# RK3566.net
KiCad netlist of a schematic drawn in Altium Designer
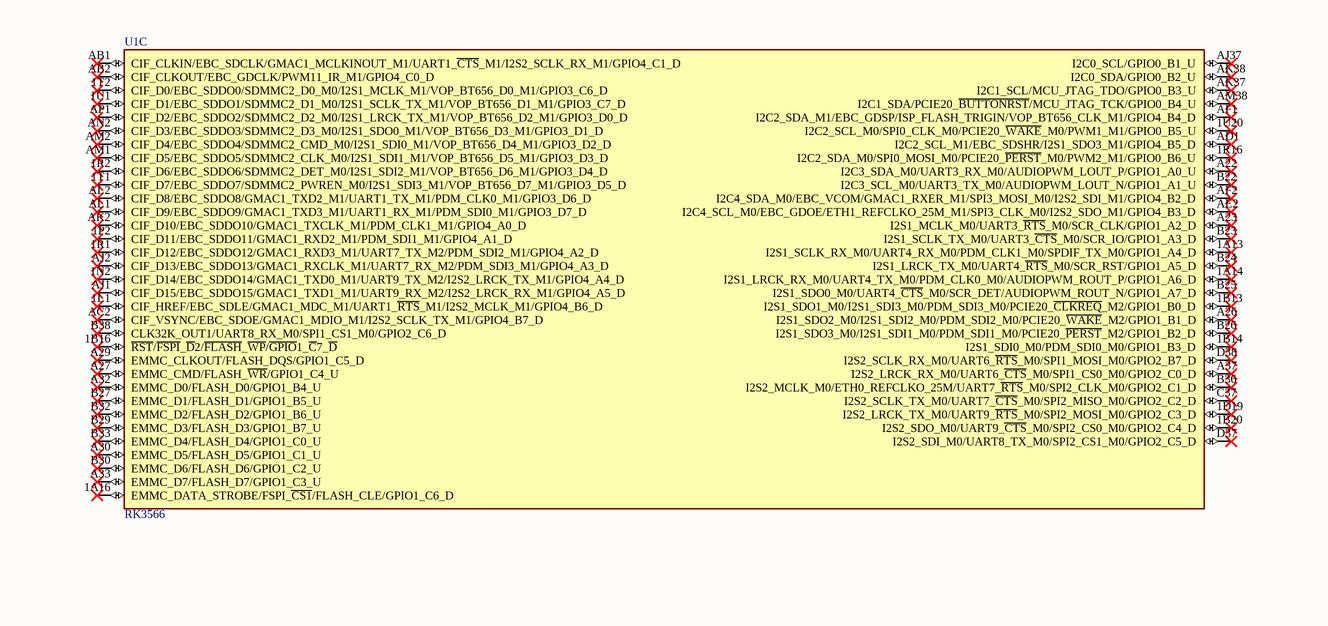
[diagram p0: RK3566.SchDoc, top left]
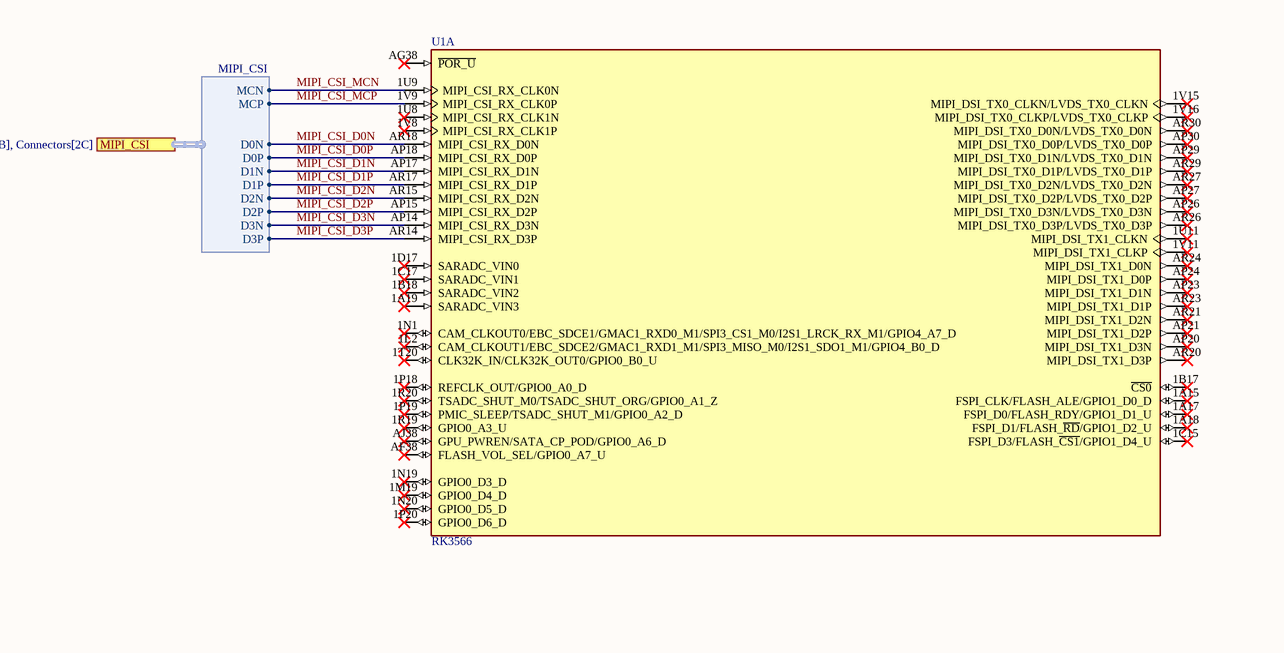
[diagram p1: RK3566.SchDoc, top right]
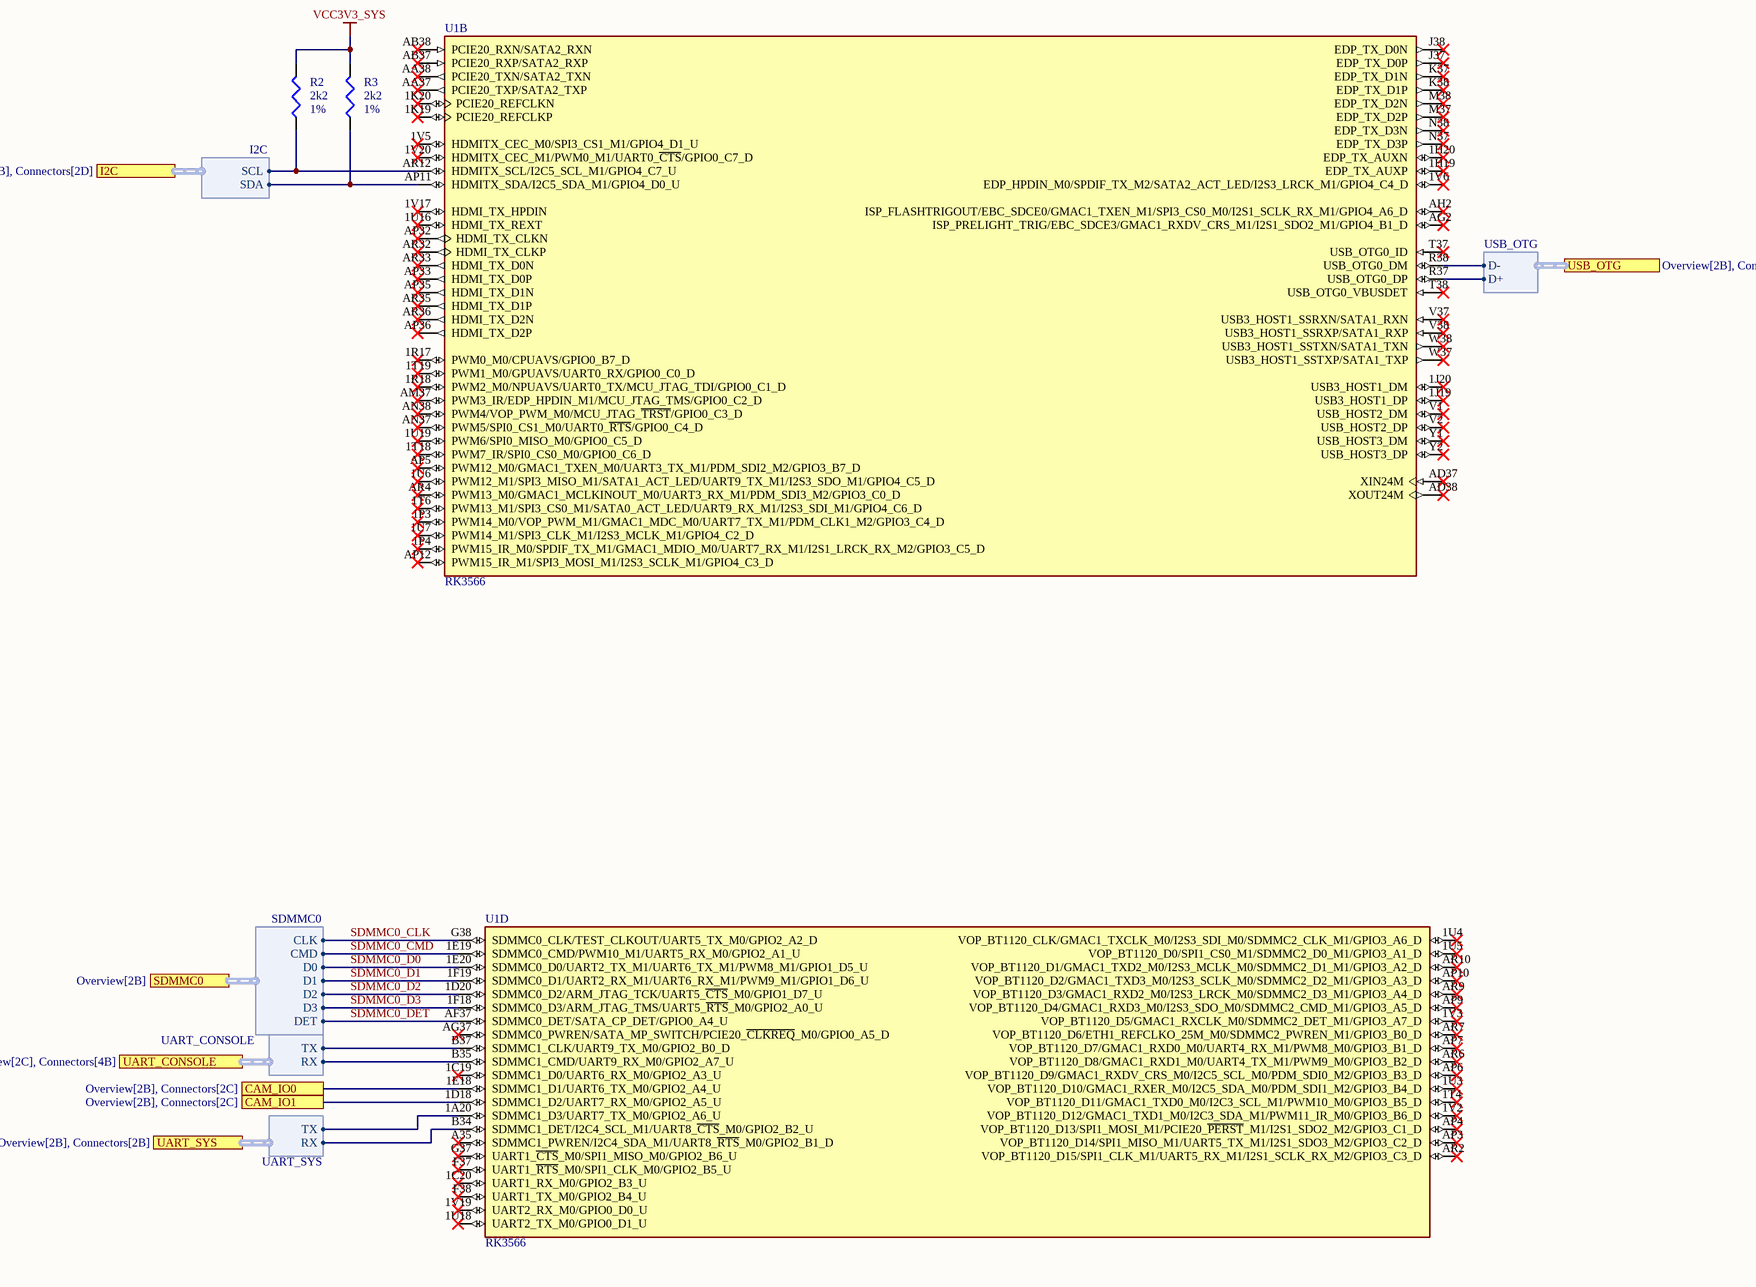
[diagram p2: RK3566.SchDoc, bottom left]
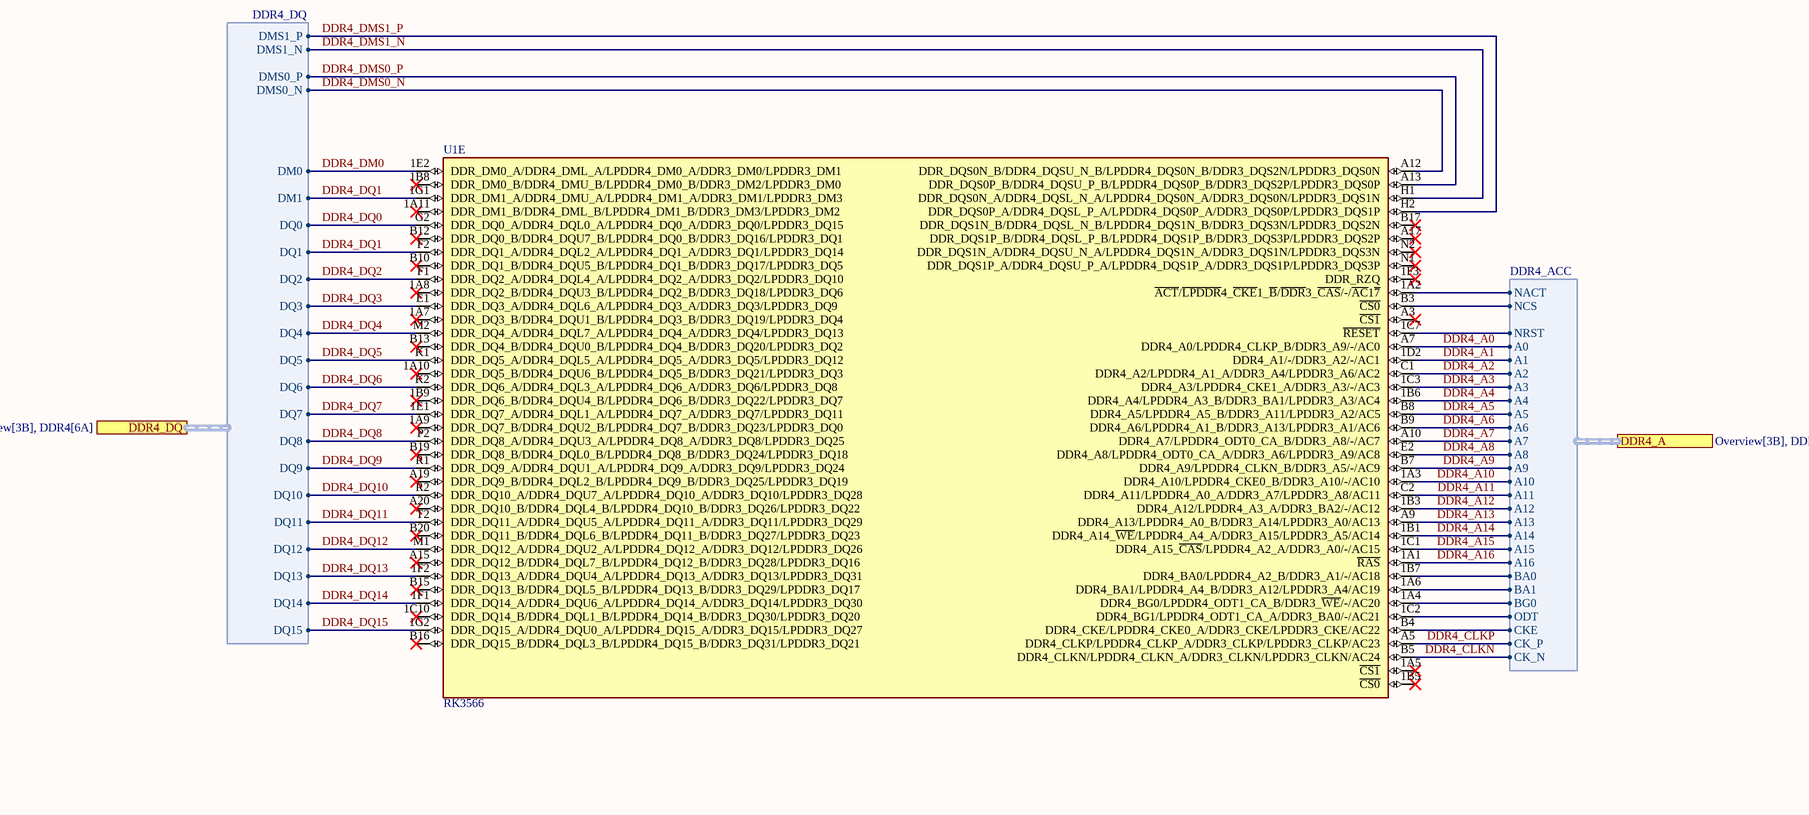
[diagram p3: RK3566.SchDoc, bottom right]

(export (version "E")
  (design (tool "Eeschema 10.0.6"))
  (components
    (comp (ref "R2")
      (value "2k2")
      (footprint "RC0402FR-075K6L")
      (description "RES 2.2k 1% 62.5mW 0402")
      (fields (field (name "TOLERANCE") "1%") (field (name "Comment") "RES 2.2K"))
      (libsource (lib "PersonalAltiumLibrary") (part "RES 2.2K"))
    )
    (comp (ref "R3")
      (value "2k2")
      (footprint "RC0402FR-075K6L")
      (description "RES 2.2k 1% 62.5mW 0402")
      (fields (field (name "TOLERANCE") "1%") (field (name "Comment") "RES 2.2K"))
      (libsource (lib "PersonalAltiumLibrary") (part "RES 2.2K"))
    )
    (comp (ref "U1")
      (value "RK3566")
      (footprint "RK3566")
      (description "high-performance and low-power quad-core application processor")
      (fields (field (name "MF") "Fuzhou Rockchip Electronics Co"))
      (libsource (lib "PersonalAltiumLibrary") (part "RK3566"))
    )
  )
  (nets
    (net (code "9") (name "/BA0") (class "Default")
      (node (ref "U1") (pin "1B7") (pinfunction "DDR4_BA0/LPDDR4_A2_B/DDR3_A1/-/AC18_1B7") (pintype "bidirectional"))
    )
    (net (code "10") (name "/BA1") (class "Default")
      (node (ref "U1") (pin "1A6") (pinfunction "DDR4_BA1/LPDDR4_A4_B/DDR3_A12/LPDDR3_A4/AC19_1A6") (pintype "bidirectional"))
    )
    (net (code "11") (name "/BG0") (class "Default")
      (node (ref "U1") (pin "1A4") (pinfunction "DDR4_BG0/LPDDR4_ODT1_CA_B/DDR3_~{WE}/-/AC20_1A4") (pintype "bidirectional"))
    )
    (net (code "12") (name "/CAM_IO0") (class "Default")
      (node (ref "U1") (pin "1E18") (pinfunction "SDMMC1_D1/UART6_TX_M0/GPIO2_A4_U_1E18") (pintype "bidirectional"))
    )
    (net (code "13") (name "/CAM_IO1") (class "Default")
      (node (ref "U1") (pin "1D18") (pinfunction "SDMMC1_D2/UART7_RX_M0/GPIO2_A5_U_1D18") (pintype "bidirectional"))
    )
    (net (code "14") (name "/CKE") (class "Default")
      (node (ref "U1") (pin "B4") (pinfunction "DDR4_CKE/LPDDR4_CKE0_A/DDR3_CKE/LPDDR3_CKE/AC22_B4") (pintype "bidirectional"))
    )
    (net (code "15") (name "/D+") (class "Default")
      (node (ref "U1") (pin "R37") (pinfunction "USB_OTG0_DP_R37") (pintype "bidirectional"))
    )
    (net (code "16") (name "/D-") (class "Default")
      (node (ref "U1") (pin "R38") (pinfunction "USB_OTG0_DM_R38") (pintype "bidirectional"))
    )
    (net (code "17") (name "/DDR4_A0") (class "Default")
      (node (ref "U1") (pin "A7") (pinfunction "DDR4_A0/LPDDR4_CLKP_B/DDR3_A9/-/AC0_A7") (pintype "bidirectional"))
    )
    (net (code "18") (name "/DDR4_A1") (class "Default")
      (node (ref "U1") (pin "1D2") (pinfunction "DDR4_A1/-/DDR3_A2/-/AC1_1D2") (pintype "bidirectional"))
    )
    (net (code "19") (name "/DDR4_A2") (class "Default")
      (node (ref "U1") (pin "C1") (pinfunction "DDR4_A2/LPDDR4_A1_A/DDR3_A4/LPDDR3_A6/AC2_C1") (pintype "bidirectional"))
    )
    (net (code "20") (name "/DDR4_A3") (class "Default")
      (node (ref "U1") (pin "1C3") (pinfunction "DDR4_A3/LPDDR4_CKE1_A/DDR3_A3/-/AC3_1C3") (pintype "bidirectional"))
    )
    (net (code "21") (name "/DDR4_A4") (class "Default")
      (node (ref "U1") (pin "1B6") (pinfunction "DDR4_A4/LPDDR4_A3_B/DDR3_BA1/LPDDR3_A3/AC4_1B6") (pintype "bidirectional"))
    )
    (net (code "22") (name "/DDR4_A5") (class "Default")
      (node (ref "U1") (pin "B8") (pinfunction "DDR4_A5/LPDDR4_A5_B/DDR3_A11/LPDDR3_A2/AC5_B8") (pintype "bidirectional"))
    )
    (net (code "23") (name "/DDR4_A6") (class "Default")
      (node (ref "U1") (pin "B9") (pinfunction "DDR4_A6/LPDDR4_A1_B/DDR3_A13/LPDDR3_A1/AC6_B9") (pintype "bidirectional"))
    )
    (net (code "24") (name "/DDR4_A7") (class "Default")
      (node (ref "U1") (pin "A10") (pinfunction "DDR4_A7/LPDDR4_ODT0_CA_B/DDR3_A8/-/AC7_A10") (pintype "bidirectional"))
    )
    (net (code "25") (name "/DDR4_A8") (class "Default")
      (node (ref "U1") (pin "E2") (pinfunction "DDR4_A8/LPDDR4_ODT0_CA_A/DDR3_A6/LPDDR3_A9/AC8_E2") (pintype "bidirectional"))
    )
    (net (code "26") (name "/DDR4_A9") (class "Default")
      (node (ref "U1") (pin "B7") (pinfunction "DDR4_A9/LPDDR4_CLKN_B/DDR3_A5/-/AC9_B7") (pintype "bidirectional"))
    )
    (net (code "27") (name "/DDR4_A10") (class "Default")
      (node (ref "U1") (pin "1A3") (pinfunction "DDR4_A10/LPDDR4_CKE0_B/DDR3_A10/-/AC10_1A3") (pintype "bidirectional"))
    )
    (net (code "28") (name "/DDR4_A11") (class "Default")
      (node (ref "U1") (pin "C2") (pinfunction "DDR4_A11/LPDDR4_A0_A/DDR3_A7/LPDDR3_A8/AC11_C2") (pintype "bidirectional"))
    )
    (net (code "29") (name "/DDR4_A12") (class "Default")
      (node (ref "U1") (pin "1B3") (pinfunction "DDR4_A12/LPDDR4_A3_A/DDR3_BA2/-/AC12_1B3") (pintype "bidirectional"))
    )
    (net (code "30") (name "/DDR4_A13") (class "Default")
      (node (ref "U1") (pin "A9") (pinfunction "DDR4_A13/LPDDR4_A0_B/DDR3_A14/LPDDR3_A0/AC13_A9") (pintype "bidirectional"))
    )
    (net (code "31") (name "/DDR4_A14") (class "Default")
      (node (ref "U1") (pin "1B1") (pinfunction "DDR4_A14_~{WE}/LPDDR4_A4_A/DDR3_A15/LPDDR3_A5/AC14_1B1") (pintype "bidirectional"))
    )
    (net (code "32") (name "/DDR4_A15") (class "Default")
      (node (ref "U1") (pin "1C1") (pinfunction "DDR4_A15_~{CAS}/LPDDR4_A2_A/DDR3_A0/-/AC15_1C1") (pintype "bidirectional"))
    )
    (net (code "33") (name "/DDR4_A16") (class "Default")
      (node (ref "U1") (pin "1A1") (pinfunction "~{RAS}_1A1") (pintype "bidirectional"))
    )
    (net (code "34") (name "/DDR4_CLKN") (class "Default")
      (node (ref "U1") (pin "B5") (pinfunction "DDR4_CLKN/LPDDR4_CLKN_A/DDR3_CLKN/LPDDR3_CLKN/AC24_B5") (pintype "bidirectional"))
    )
    (net (code "35") (name "/DDR4_CLKP") (class "Default")
      (node (ref "U1") (pin "A5") (pinfunction "DDR4_CLKP/LPDDR4_CLKP_A/DDR3_CLKP/LPDDR3_CLKP/AC23_A5") (pintype "bidirectional"))
    )
    (net (code "36") (name "/DDR4_DM0") (class "Default")
      (node (ref "U1") (pin "1E2") (pinfunction "DDR_DM0_A/DDR4_DML_A/LPDDR4_DM0_A/DDR3_DM0/LPDDR3_DM1_1E2") (pintype "bidirectional"))
    )
    (net (code "37") (name "/DDR4_DMS0_N") (class "Default")
      (node (ref "U1") (pin "A12") (pinfunction "DDR_DQS0N_B/DDR4_DQSU_N_B/LPDDR4_DQS0N_B/DDR3_DQS2N/LPDDR3_DQS0N_A12") (pintype "bidirectional"))
    )
    (net (code "38") (name "/DDR4_DMS0_P") (class "Default")
      (node (ref "U1") (pin "A13") (pinfunction "DDR_DQS0P_B/DDR4_DQSU_P_B/LPDDR4_DQS0P_B/DDR3_DQS2P/LPDDR3_DQS0P_A13") (pintype "bidirectional"))
    )
    (net (code "39") (name "/DDR4_DMS1_N") (class "Default")
      (node (ref "U1") (pin "H1") (pinfunction "DDR_DQS0N_A/DDR4_DQSL_N_A/LPDDR4_DQS0N_A/DDR3_DQS0N/LPDDR3_DQS1N_H1") (pintype "bidirectional"))
    )
    (net (code "40") (name "/DDR4_DMS1_P") (class "Default")
      (node (ref "U1") (pin "H2") (pinfunction "DDR_DQS0P_A/DDR4_DQSL_P_A/LPDDR4_DQS0P_A/DDR3_DQS0P/LPDDR3_DQS1P_H2") (pintype "bidirectional"))
    )
    (net (code "41") (name "/DDR4_DQ0") (class "Default")
      (node (ref "U1") (pin "G2") (pinfunction "DDR_DQ0_A/DDR4_DQL0_A/LPDDR4_DQ0_A/DDR3_DQ0/LPDDR3_DQ15_G2") (pintype "bidirectional"))
    )
    (net (code "42") (name "/DDR4_DQ1") (class "Default")
      (node (ref "U1") (pin "1G1") (pinfunction "DDR_DM1_A/DDR4_DMU_A/LPDDR4_DM1_A/DDR3_DM1/LPDDR3_DM3_1G1") (pintype "bidirectional"))
      (node (ref "U1") (pin "F2") (pinfunction "DDR_DQ1_A/DDR4_DQL2_A/LPDDR4_DQ1_A/DDR3_DQ1/LPDDR3_DQ14_F2") (pintype "bidirectional"))
    )
    (net (code "43") (name "/DDR4_DQ2") (class "Default")
      (node (ref "U1") (pin "F1") (pinfunction "DDR_DQ2_A/DDR4_DQL4_A/LPDDR4_DQ2_A/DDR3_DQ2/LPDDR3_DQ10_F1") (pintype "bidirectional"))
    )
    (net (code "44") (name "/DDR4_DQ3") (class "Default")
      (node (ref "U1") (pin "E1") (pinfunction "DDR_DQ3_A/DDR4_DQL6_A/LPDDR4_DQ3_A/DDR3_DQ3/LPDDR3_DQ9_E1") (pintype "bidirectional"))
    )
    (net (code "45") (name "/DDR4_DQ4") (class "Default")
      (node (ref "U1") (pin "M2") (pinfunction "DDR_DQ4_A/DDR4_DQL7_A/LPDDR4_DQ4_A/DDR3_DQ4/LPDDR3_DQ13_M2") (pintype "bidirectional"))
    )
    (net (code "46") (name "/DDR4_DQ5") (class "Default")
      (node (ref "U1") (pin "K1") (pinfunction "DDR_DQ5_A/DDR4_DQL5_A/LPDDR4_DQ5_A/DDR3_DQ5/LPDDR3_DQ12_K1") (pintype "bidirectional"))
    )
    (net (code "47") (name "/DDR4_DQ6") (class "Default")
      (node (ref "U1") (pin "K2") (pinfunction "DDR_DQ6_A/DDR4_DQL3_A/LPDDR4_DQ6_A/DDR3_DQ6/LPDDR3_DQ8_K2") (pintype "bidirectional"))
    )
    (net (code "48") (name "/DDR4_DQ7") (class "Default")
      (node (ref "U1") (pin "1E1") (pinfunction "DDR_DQ7_A/DDR4_DQL1_A/LPDDR4_DQ7_A/DDR3_DQ7/LPDDR3_DQ11_1E1") (pintype "bidirectional"))
    )
    (net (code "49") (name "/DDR4_DQ8") (class "Default")
      (node (ref "U1") (pin "P2") (pinfunction "DDR_DQ8_A/DDR4_DQU3_A/LPDDR4_DQ8_A/DDR3_DQ8/LPDDR3_DQ25_P2") (pintype "bidirectional"))
    )
    (net (code "50") (name "/DDR4_DQ9") (class "Default")
      (node (ref "U1") (pin "R1") (pinfunction "DDR_DQ9_A/DDR4_DQU1_A/LPDDR4_DQ9_A/DDR3_DQ9/LPDDR3_DQ24_R1") (pintype "bidirectional"))
    )
    (net (code "51") (name "/DDR4_DQ10") (class "Default")
      (node (ref "U1") (pin "R2") (pinfunction "DDR_DQ10_A/DDR4_DQU7_A/LPDDR4_DQ10_A/DDR3_DQ10/LPDDR3_DQ28_R2") (pintype "bidirectional"))
    )
    (net (code "52") (name "/DDR4_DQ11") (class "Default")
      (node (ref "U1") (pin "T2") (pinfunction "DDR_DQ11_A/DDR4_DQU5_A/LPDDR4_DQ11_A/DDR3_DQ11/LPDDR3_DQ29_T2") (pintype "bidirectional"))
    )
    (net (code "53") (name "/DDR4_DQ12") (class "Default")
      (node (ref "U1") (pin "M1") (pinfunction "DDR_DQ12_A/DDR4_DQU2_A/LPDDR4_DQ12_A/DDR3_DQ12/LPDDR3_DQ26_M1") (pintype "bidirectional"))
    )
    (net (code "54") (name "/DDR4_DQ13") (class "Default")
      (node (ref "U1") (pin "1F2") (pinfunction "DDR_DQ13_A/DDR4_DQU4_A/LPDDR4_DQ13_A/DDR3_DQ13/LPDDR3_DQ31_1F2") (pintype "bidirectional"))
    )
    (net (code "55") (name "/DDR4_DQ14") (class "Default")
      (node (ref "U1") (pin "1F1") (pinfunction "DDR_DQ14_A/DDR4_DQU6_A/LPDDR4_DQ14_A/DDR3_DQ14/LPDDR3_DQ30_1F1") (pintype "bidirectional"))
    )
    (net (code "56") (name "/DDR4_DQ15") (class "Default")
      (node (ref "U1") (pin "1G2") (pinfunction "DDR_DQ15_A/DDR4_DQU0_A/LPDDR4_DQ15_A/DDR3_DQ15/LPDDR3_DQ27_1G2") (pintype "bidirectional"))
    )
    (net (code "57") (name "/MIPI_CSI_D0N") (class "Default")
      (node (ref "U1") (pin "AR18") (pinfunction "MIPI_CSI_RX_D0N_AR18") (pintype "input"))
    )
    (net (code "58") (name "/MIPI_CSI_D0P") (class "Default")
      (node (ref "U1") (pin "AP18") (pinfunction "MIPI_CSI_RX_D0P_AP18") (pintype "input"))
    )
    (net (code "59") (name "/MIPI_CSI_D1N") (class "Default")
      (node (ref "U1") (pin "AP17") (pinfunction "MIPI_CSI_RX_D1N_AP17") (pintype "input"))
    )
    (net (code "60") (name "/MIPI_CSI_D1P") (class "Default")
      (node (ref "U1") (pin "AR17") (pinfunction "MIPI_CSI_RX_D1P_AR17") (pintype "input"))
    )
    (net (code "61") (name "/MIPI_CSI_D2N") (class "Default")
      (node (ref "U1") (pin "AR15") (pinfunction "MIPI_CSI_RX_D2N_AR15") (pintype "input"))
    )
    (net (code "62") (name "/MIPI_CSI_D2P") (class "Default")
      (node (ref "U1") (pin "AP15") (pinfunction "MIPI_CSI_RX_D2P_AP15") (pintype "input"))
    )
    (net (code "63") (name "/MIPI_CSI_D3N") (class "Default")
      (node (ref "U1") (pin "AP14") (pinfunction "MIPI_CSI_RX_D3N_AP14") (pintype "input"))
    )
    (net (code "64") (name "/MIPI_CSI_D3P") (class "Default")
      (node (ref "U1") (pin "AR14") (pinfunction "MIPI_CSI_RX_D3P_AR14") (pintype "input"))
    )
    (net (code "65") (name "/MIPI_CSI_MCN") (class "Default")
      (node (ref "U1") (pin "1U9") (pinfunction "MIPI_CSI_RX_CLK0N_1U9") (pintype "input"))
    )
    (net (code "66") (name "/MIPI_CSI_MCP") (class "Default")
      (node (ref "U1") (pin "1V9") (pinfunction "MIPI_CSI_RX_CLK0P_1V9") (pintype "input"))
    )
    (net (code "67") (name "/NACT") (class "Default")
      (node (ref "U1") (pin "1A2") (pinfunction "~{ACT}/~{LPDDR}4_~{CKE}1_~{B}/~{DDR}3_~{CAS}/-/~{AC}1~{7}_1A2") (pintype "bidirectional"))
    )
    (net (code "68") (name "/NCS") (class "Default")
      (node (ref "U1") (pin "B3") (pinfunction "~{CS0}_B3") (pintype "bidirectional"))
    )
    (net (code "69") (name "/NRST") (class "Default")
      (node (ref "U1") (pin "1C7") (pinfunction "~{RESET}_1C7") (pintype "bidirectional"))
    )
    (net (code "70") (name "/ODT") (class "Default")
      (node (ref "U1") (pin "1C2") (pinfunction "DDR4_BG1/LPDDR4_ODT1_CA_A/DDR3_BA0/-/AC21_1C2") (pintype "bidirectional"))
    )
    (net (code "71") (name "/SCL") (class "Default")
      (node (ref "R2") (pin "2") (pinfunction "2_2") (pintype "passive"))
      (node (ref "U1") (pin "AR12") (pinfunction "HDMITX_SCL/I2C5_SCL_M1/GPIO4_C7_U_AR12") (pintype "bidirectional"))
    )
    (net (code "72") (name "/SDA") (class "Default")
      (node (ref "R3") (pin "2") (pinfunction "2_2") (pintype "passive"))
      (node (ref "U1") (pin "AP11") (pinfunction "HDMITX_SDA/I2C5_SDA_M1/GPIO4_D0_U_AP11") (pintype "bidirectional"))
    )
    (net (code "73") (name "/SDMMC0_CLK") (class "Default")
      (node (ref "U1") (pin "G38") (pinfunction "SDMMC0_CLK/TEST_CLKOUT/UART5_TX_M0/GPIO2_A2_D_G38") (pintype "bidirectional"))
    )
    (net (code "74") (name "/SDMMC0_CMD") (class "Default")
      (node (ref "U1") (pin "1E19") (pinfunction "SDMMC0_CMD/PWM10_M1/UART5_RX_M0/GPIO2_A1_U_1E19") (pintype "bidirectional"))
    )
    (net (code "75") (name "/SDMMC0_D0") (class "Default")
      (node (ref "U1") (pin "1E20") (pinfunction "SDMMC0_D0/UART2_TX_M1/UART6_TX_M1/PWM8_M1/GPIO1_D5_U_1E20") (pintype "bidirectional"))
    )
    (net (code "76") (name "/SDMMC0_D1") (class "Default")
      (node (ref "U1") (pin "1F19") (pinfunction "SDMMC0_D1/UART2_RX_M1/UART6_RX_M1/PWM9_M1/GPIO1_D6_U_1F19") (pintype "bidirectional"))
    )
    (net (code "77") (name "/SDMMC0_D2") (class "Default")
      (node (ref "U1") (pin "1D20") (pinfunction "SDMMC0_D2/ARM_JTAG_TCK/UART5_~{CTS}_M0/GPIO1_D7_U_1D20") (pintype "bidirectional"))
    )
    (net (code "78") (name "/SDMMC0_D3") (class "Default")
      (node (ref "U1") (pin "1F18") (pinfunction "SDMMC0_D3/ARM_JTAG_TMS/UART5_~{RTS}_M0/GPIO2_A0_U_1F18") (pintype "bidirectional"))
    )
    (net (code "79") (name "/SDMMC0_DET") (class "Default")
      (node (ref "U1") (pin "AF37") (pinfunction "SDMMC0_DET/SATA_CP_DET/GPIO0_A4_U_AF37") (pintype "bidirectional"))
    )
    (net (code "88") (name "VCC3V3_SYS") (class "Default")
      (node (ref "R2") (pin "1") (pinfunction "1_1") (pintype "passive"))
      (node (ref "R3") (pin "1") (pinfunction "1_1") (pintype "passive"))
    )
    (net (code "89") (name "unconnected-(U1A-CAM_CLKOUT0{slash}EBC_SDCE1{slash}GMAC1_RXD0_M1{slash}SPI3_CS1_M0{slash}I2S1_LRCK_RX_M1{slash}GPIO4_A7_D-Pad1N1)") (class "Default")
      (node (ref "U1") (pin "1N1") (pinfunction "CAM_CLKOUT0/EBC_SDCE1/GMAC1_RXD0_M1/SPI3_CS1_M0/I2S1_LRCK_RX_M1/GPIO4_A7_D_1N1") (pintype "bidirectional+no_connect"))
    )
    (net (code "90") (name "unconnected-(U1A-CAM_CLKOUT1{slash}EBC_SDCE2{slash}GMAC1_RXD1_M1{slash}SPI3_MISO_M0{slash}I2S1_SDO1_M1{slash}GPIO4_B0_D-Pad1L2)") (class "Default")
      (node (ref "U1") (pin "1L2") (pinfunction "CAM_CLKOUT1/EBC_SDCE2/GMAC1_RXD1_M1/SPI3_MISO_M0/I2S1_SDO1_M1/GPIO4_B0_D_1L2") (pintype "bidirectional+no_connect"))
    )
    (net (code "91") (name "unconnected-(U1A-CLK32K_IN{slash}CLK32K_OUT0{slash}GPIO0_B0_U-Pad1T20)") (class "Default")
      (node (ref "U1") (pin "1T20") (pinfunction "CLK32K_IN/CLK32K_OUT0/GPIO0_B0_U_1T20") (pintype "bidirectional+no_connect"))
    )
    (net (code "92") (name "unconnected-(U1A-FLASH_VOL_SEL{slash}GPIO0_A7_U-PadAF38)") (class "Default")
      (node (ref "U1") (pin "AF38") (pinfunction "FLASH_VOL_SEL/GPIO0_A7_U_AF38") (pintype "bidirectional+no_connect"))
    )
    (net (code "93") (name "unconnected-(U1A-FSPI_CLK{slash}FLASH_ALE{slash}GPIO1_D0_D-Pad1A15)") (class "Default")
      (node (ref "U1") (pin "1A15") (pinfunction "FSPI_CLK/FLASH_ALE/GPIO1_D0_D_1A15") (pintype "bidirectional+no_connect"))
    )
    (net (code "94") (name "unconnected-(U1A-FSPI_D0{slash}FLASH_RDY{slash}GPIO1_D1_U-Pad1A17)") (class "Default")
      (node (ref "U1") (pin "1A17") (pinfunction "FSPI_D0/FLASH_RDY/GPIO1_D1_U_1A17") (pintype "bidirectional+no_connect"))
    )
    (net (code "95") (name "unconnected-(U1A-FSPI_D1{slash}FLASH_~{RD}{slash}GPIO1_D2_U-Pad1A18)") (class "Default")
      (node (ref "U1") (pin "1A18") (pinfunction "FSPI_D1/FLASH_~{RD}/GPIO1_D2_U_1A18") (pintype "bidirectional+no_connect"))
    )
    (net (code "96") (name "unconnected-(U1A-FSPI_D3{slash}FLASH_~{CS1}{slash}GPIO1_D4_U-Pad1C15)") (class "Default")
      (node (ref "U1") (pin "1C15") (pinfunction "FSPI_D3/FLASH_~{CS1}/GPIO1_D4_U_1C15") (pintype "bidirectional+no_connect"))
    )
    (net (code "97") (name "unconnected-(U1A-GPIO0_A3_U-Pad1R19)") (class "Default")
      (node (ref "U1") (pin "1R19") (pinfunction "GPIO0_A3_U_1R19") (pintype "bidirectional+no_connect"))
    )
    (net (code "98") (name "unconnected-(U1A-GPIO0_D3_D-Pad1N19)") (class "Default")
      (node (ref "U1") (pin "1N19") (pinfunction "GPIO0_D3_D_1N19") (pintype "bidirectional+no_connect"))
    )
    (net (code "99") (name "unconnected-(U1A-GPIO0_D4_D-Pad1M19)") (class "Default")
      (node (ref "U1") (pin "1M19") (pinfunction "GPIO0_D4_D_1M19") (pintype "bidirectional+no_connect"))
    )
    (net (code "100") (name "unconnected-(U1A-GPIO0_D5_D-Pad1N20)") (class "Default")
      (node (ref "U1") (pin "1N20") (pinfunction "GPIO0_D5_D_1N20") (pintype "bidirectional+no_connect"))
    )
    (net (code "101") (name "unconnected-(U1A-GPIO0_D6_D-Pad1P20)") (class "Default")
      (node (ref "U1") (pin "1P20") (pinfunction "GPIO0_D6_D_1P20") (pintype "bidirectional+no_connect"))
    )
    (net (code "102") (name "unconnected-(U1A-GPU_PWREN{slash}SATA_CP_POD{slash}GPIO0_A6_D-PadAJ38)") (class "Default")
      (node (ref "U1") (pin "AJ38") (pinfunction "GPU_PWREN/SATA_CP_POD/GPIO0_A6_D_AJ38") (pintype "bidirectional+no_connect"))
    )
    (net (code "103") (name "unconnected-(U1A-MIPI_CSI_RX_CLK1N-Pad1U8)") (class "Default")
      (node (ref "U1") (pin "1U8") (pinfunction "MIPI_CSI_RX_CLK1N_1U8") (pintype "input+no_connect"))
    )
    (net (code "104") (name "unconnected-(U1A-MIPI_CSI_RX_CLK1P-Pad1V8)") (class "Default")
      (node (ref "U1") (pin "1V8") (pinfunction "MIPI_CSI_RX_CLK1P_1V8") (pintype "input+no_connect"))
    )
    (net (code "105") (name "unconnected-(U1A-MIPI_DSI_TX0_CLKN{slash}LVDS_TX0_CLKN-Pad1V15)") (class "Default")
      (node (ref "U1") (pin "1V15") (pinfunction "MIPI_DSI_TX0_CLKN/LVDS_TX0_CLKN_1V15") (pintype "output+no_connect"))
    )
    (net (code "106") (name "unconnected-(U1A-MIPI_DSI_TX0_CLKP{slash}LVDS_TX0_CLKP-Pad1V16)") (class "Default")
      (node (ref "U1") (pin "1V16") (pinfunction "MIPI_DSI_TX0_CLKP/LVDS_TX0_CLKP_1V16") (pintype "output+no_connect"))
    )
    (net (code "107") (name "unconnected-(U1A-MIPI_DSI_TX0_D0N{slash}LVDS_TX0_D0N-PadAR30)") (class "Default")
      (node (ref "U1") (pin "AR30") (pinfunction "MIPI_DSI_TX0_D0N/LVDS_TX0_D0N_AR30") (pintype "output+no_connect"))
    )
    (net (code "108") (name "unconnected-(U1A-MIPI_DSI_TX0_D0P{slash}LVDS_TX0_D0P-PadAP30)") (class "Default")
      (node (ref "U1") (pin "AP30") (pinfunction "MIPI_DSI_TX0_D0P/LVDS_TX0_D0P_AP30") (pintype "output+no_connect"))
    )
    (net (code "109") (name "unconnected-(U1A-MIPI_DSI_TX0_D1N{slash}LVDS_TX0_D1N-PadAP29)") (class "Default")
      (node (ref "U1") (pin "AP29") (pinfunction "MIPI_DSI_TX0_D1N/LVDS_TX0_D1N_AP29") (pintype "output+no_connect"))
    )
    (net (code "110") (name "unconnected-(U1A-MIPI_DSI_TX0_D1P{slash}LVDS_TX0_D1P-PadAR29)") (class "Default")
      (node (ref "U1") (pin "AR29") (pinfunction "MIPI_DSI_TX0_D1P/LVDS_TX0_D1P_AR29") (pintype "output+no_connect"))
    )
    (net (code "111") (name "unconnected-(U1A-MIPI_DSI_TX0_D2N{slash}LVDS_TX0_D2N-PadAR27)") (class "Default")
      (node (ref "U1") (pin "AR27") (pinfunction "MIPI_DSI_TX0_D2N/LVDS_TX0_D2N_AR27") (pintype "output+no_connect"))
    )
    (net (code "112") (name "unconnected-(U1A-MIPI_DSI_TX0_D2P{slash}LVDS_TX0_D2P-PadAP27)") (class "Default")
      (node (ref "U1") (pin "AP27") (pinfunction "MIPI_DSI_TX0_D2P/LVDS_TX0_D2P_AP27") (pintype "output+no_connect"))
    )
    (net (code "113") (name "unconnected-(U1A-MIPI_DSI_TX0_D3N{slash}LVDS_TX0_D3N-PadAP26)") (class "Default")
      (node (ref "U1") (pin "AP26") (pinfunction "MIPI_DSI_TX0_D3N/LVDS_TX0_D3N_AP26") (pintype "output+no_connect"))
    )
    (net (code "114") (name "unconnected-(U1A-MIPI_DSI_TX0_D3P{slash}LVDS_TX0_D3P-PadAR26)") (class "Default")
      (node (ref "U1") (pin "AR26") (pinfunction "MIPI_DSI_TX0_D3P/LVDS_TX0_D3P_AR26") (pintype "output+no_connect"))
    )
    (net (code "115") (name "unconnected-(U1A-MIPI_DSI_TX1_CLKN-Pad1U11)") (class "Default")
      (node (ref "U1") (pin "1U11") (pinfunction "MIPI_DSI_TX1_CLKN_1U11") (pintype "output+no_connect"))
    )
    (net (code "116") (name "unconnected-(U1A-MIPI_DSI_TX1_CLKP-Pad1V11)") (class "Default")
      (node (ref "U1") (pin "1V11") (pinfunction "MIPI_DSI_TX1_CLKP_1V11") (pintype "output+no_connect"))
    )
    (net (code "117") (name "unconnected-(U1A-MIPI_DSI_TX1_D0N-PadAR24)") (class "Default")
      (node (ref "U1") (pin "AR24") (pinfunction "MIPI_DSI_TX1_D0N_AR24") (pintype "output+no_connect"))
    )
    (net (code "118") (name "unconnected-(U1A-MIPI_DSI_TX1_D0P-PadAP24)") (class "Default")
      (node (ref "U1") (pin "AP24") (pinfunction "MIPI_DSI_TX1_D0P_AP24") (pintype "output+no_connect"))
    )
    (net (code "119") (name "unconnected-(U1A-MIPI_DSI_TX1_D1N-PadAP23)") (class "Default")
      (node (ref "U1") (pin "AP23") (pinfunction "MIPI_DSI_TX1_D1N_AP23") (pintype "output+no_connect"))
    )
    (net (code "120") (name "unconnected-(U1A-MIPI_DSI_TX1_D1P-PadAR23)") (class "Default")
      (node (ref "U1") (pin "AR23") (pinfunction "MIPI_DSI_TX1_D1P_AR23") (pintype "output+no_connect"))
    )
    (net (code "121") (name "unconnected-(U1A-MIPI_DSI_TX1_D2N-PadAR21)") (class "Default")
      (node (ref "U1") (pin "AR21") (pinfunction "MIPI_DSI_TX1_D2N_AR21") (pintype "output+no_connect"))
    )
    (net (code "122") (name "unconnected-(U1A-MIPI_DSI_TX1_D2P-PadAP21)") (class "Default")
      (node (ref "U1") (pin "AP21") (pinfunction "MIPI_DSI_TX1_D2P_AP21") (pintype "output+no_connect"))
    )
    (net (code "123") (name "unconnected-(U1A-MIPI_DSI_TX1_D3N-PadAP20)") (class "Default")
      (node (ref "U1") (pin "AP20") (pinfunction "MIPI_DSI_TX1_D3N_AP20") (pintype "output+no_connect"))
    )
    (net (code "124") (name "unconnected-(U1A-MIPI_DSI_TX1_D3P-PadAR20)") (class "Default")
      (node (ref "U1") (pin "AR20") (pinfunction "MIPI_DSI_TX1_D3P_AR20") (pintype "output+no_connect"))
    )
    (net (code "125") (name "unconnected-(U1A-PMIC_SLEEP{slash}TSADC_SHUT_M1{slash}GPIO0_A2_D-Pad1P19)") (class "Default")
      (node (ref "U1") (pin "1P19") (pinfunction "PMIC_SLEEP/TSADC_SHUT_M1/GPIO0_A2_D_1P19") (pintype "bidirectional+no_connect"))
    )
    (net (code "126") (name "unconnected-(U1A-REFCLK_OUT{slash}GPIO0_A0_D-Pad1P18)") (class "Default")
      (node (ref "U1") (pin "1P18") (pinfunction "REFCLK_OUT/GPIO0_A0_D_1P18") (pintype "bidirectional+no_connect"))
    )
    (net (code "127") (name "unconnected-(U1A-SARADC_VIN0-Pad1D17)") (class "Default")
      (node (ref "U1") (pin "1D17") (pinfunction "SARADC_VIN0_1D17") (pintype "input+no_connect"))
    )
    (net (code "128") (name "unconnected-(U1A-SARADC_VIN1-Pad1C17)") (class "Default")
      (node (ref "U1") (pin "1C17") (pinfunction "SARADC_VIN1_1C17") (pintype "input+no_connect"))
    )
    (net (code "129") (name "unconnected-(U1A-SARADC_VIN2-Pad1B18)") (class "Default")
      (node (ref "U1") (pin "1B18") (pinfunction "SARADC_VIN2_1B18") (pintype "input+no_connect"))
    )
    (net (code "130") (name "unconnected-(U1A-SARADC_VIN3-Pad1A19)") (class "Default")
      (node (ref "U1") (pin "1A19") (pinfunction "SARADC_VIN3_1A19") (pintype "input+no_connect"))
    )
    (net (code "131") (name "unconnected-(U1A-TSADC_SHUT_M0{slash}TSADC_SHUT_ORG{slash}GPIO0_A1_Z-Pad1R20)") (class "Default")
      (node (ref "U1") (pin "1R20") (pinfunction "TSADC_SHUT_M0/TSADC_SHUT_ORG/GPIO0_A1_Z_1R20") (pintype "bidirectional+no_connect"))
    )
    (net (code "132") (name "unconnected-(U1A-~{CS0}-Pad1B17)") (class "Default")
      (node (ref "U1") (pin "1B17") (pinfunction "~{CS0}_1B17") (pintype "bidirectional+no_connect"))
    )
    (net (code "133") (name "unconnected-(U1A-~{POR_U}-PadAG38)") (class "Default")
      (node (ref "U1") (pin "AG38") (pinfunction "~{POR_U}_AG38") (pintype "input+no_connect"))
    )
    (net (code "134") (name "unconnected-(U1B-EDP_HPDIN_M0{slash}SPDIF_TX_M2{slash}SATA2_ACT_LED{slash}I2S3_LRCK_M1{slash}GPIO4_C4_D-Pad1V6)") (class "Default")
      (node (ref "U1") (pin "1V6") (pinfunction "EDP_HPDIN_M0/SPDIF_TX_M2/SATA2_ACT_LED/I2S3_LRCK_M1/GPIO4_C4_D_1V6") (pintype "bidirectional+no_connect"))
    )
    (net (code "135") (name "unconnected-(U1B-EDP_TX_AUXN-Pad1H20)") (class "Default")
      (node (ref "U1") (pin "1H20") (pinfunction "EDP_TX_AUXN_1H20") (pintype "bidirectional+no_connect"))
    )
    (net (code "136") (name "unconnected-(U1B-EDP_TX_AUXP-Pad1H19)") (class "Default")
      (node (ref "U1") (pin "1H19") (pinfunction "EDP_TX_AUXP_1H19") (pintype "bidirectional+no_connect"))
    )
    (net (code "137") (name "unconnected-(U1B-EDP_TX_D0N-PadJ38)") (class "Default")
      (node (ref "U1") (pin "J38") (pinfunction "EDP_TX_D0N_J38") (pintype "output+no_connect"))
    )
    (net (code "138") (name "unconnected-(U1B-EDP_TX_D0P-PadJ37)") (class "Default")
      (node (ref "U1") (pin "J37") (pinfunction "EDP_TX_D0P_J37") (pintype "output+no_connect"))
    )
    (net (code "139") (name "unconnected-(U1B-EDP_TX_D1N-PadK37)") (class "Default")
      (node (ref "U1") (pin "K37") (pinfunction "EDP_TX_D1N_K37") (pintype "output+no_connect"))
    )
    (net (code "140") (name "unconnected-(U1B-EDP_TX_D1P-PadK38)") (class "Default")
      (node (ref "U1") (pin "K38") (pinfunction "EDP_TX_D1P_K38") (pintype "output+no_connect"))
    )
    (net (code "141") (name "unconnected-(U1B-EDP_TX_D2N-PadM38)") (class "Default")
      (node (ref "U1") (pin "M38") (pinfunction "EDP_TX_D2N_M38") (pintype "output+no_connect"))
    )
    (net (code "142") (name "unconnected-(U1B-EDP_TX_D2P-PadM37)") (class "Default")
      (node (ref "U1") (pin "M37") (pinfunction "EDP_TX_D2P_M37") (pintype "output+no_connect"))
    )
    (net (code "143") (name "unconnected-(U1B-EDP_TX_D3N-PadN38)") (class "Default")
      (node (ref "U1") (pin "N38") (pinfunction "EDP_TX_D3N_N38") (pintype "output+no_connect"))
    )
    (net (code "144") (name "unconnected-(U1B-EDP_TX_D3P-PadN37)") (class "Default")
      (node (ref "U1") (pin "N37") (pinfunction "EDP_TX_D3P_N37") (pintype "output+no_connect"))
    )
    (net (code "145") (name "unconnected-(U1B-HDMITX_CEC_M0{slash}SPI3_CS1_M1{slash}GPIO4_D1_U-Pad1V5)") (class "Default")
      (node (ref "U1") (pin "1V5") (pinfunction "HDMITX_CEC_M0/SPI3_CS1_M1/GPIO4_D1_U_1V5") (pintype "bidirectional+no_connect"))
    )
    (net (code "146") (name "unconnected-(U1B-HDMITX_CEC_M1{slash}PWM0_M1{slash}UART0_~{CTS}{slash}GPIO0_C7_D-Pad1V20)") (class "Default")
      (node (ref "U1") (pin "1V20") (pinfunction "HDMITX_CEC_M1/PWM0_M1/UART0_~{CTS}/GPIO0_C7_D_1V20") (pintype "bidirectional+no_connect"))
    )
    (net (code "147") (name "unconnected-(U1B-HDMI_TX_CLKN-PadAP32)") (class "Default")
      (node (ref "U1") (pin "AP32") (pinfunction "HDMI_TX_CLKN_AP32") (pintype "output+no_connect"))
    )
    (net (code "148") (name "unconnected-(U1B-HDMI_TX_CLKP-PadAR32)") (class "Default")
      (node (ref "U1") (pin "AR32") (pinfunction "HDMI_TX_CLKP_AR32") (pintype "output+no_connect"))
    )
    (net (code "149") (name "unconnected-(U1B-HDMI_TX_D0N-PadAR33)") (class "Default")
      (node (ref "U1") (pin "AR33") (pinfunction "HDMI_TX_D0N_AR33") (pintype "output+no_connect"))
    )
    (net (code "150") (name "unconnected-(U1B-HDMI_TX_D0P-PadAP33)") (class "Default")
      (node (ref "U1") (pin "AP33") (pinfunction "HDMI_TX_D0P_AP33") (pintype "output+no_connect"))
    )
    (net (code "151") (name "unconnected-(U1B-HDMI_TX_D1N-PadAP35)") (class "Default")
      (node (ref "U1") (pin "AP35") (pinfunction "HDMI_TX_D1N_AP35") (pintype "output+no_connect"))
    )
    (net (code "152") (name "unconnected-(U1B-HDMI_TX_D1P-PadAR35)") (class "Default")
      (node (ref "U1") (pin "AR35") (pinfunction "HDMI_TX_D1P_AR35") (pintype "output+no_connect"))
    )
    (net (code "153") (name "unconnected-(U1B-HDMI_TX_D2N-PadAR36)") (class "Default")
      (node (ref "U1") (pin "AR36") (pinfunction "HDMI_TX_D2N_AR36") (pintype "output+no_connect"))
    )
    (net (code "154") (name "unconnected-(U1B-HDMI_TX_D2P-PadAP36)") (class "Default")
      (node (ref "U1") (pin "AP36") (pinfunction "HDMI_TX_D2P_AP36") (pintype "output+no_connect"))
    )
    (net (code "155") (name "unconnected-(U1B-HDMI_TX_HPDIN-Pad1V17)") (class "Default")
      (node (ref "U1") (pin "1V17") (pinfunction "HDMI_TX_HPDIN_1V17") (pintype "bidirectional+no_connect"))
    )
    (net (code "156") (name "unconnected-(U1B-HDMI_TX_REXT-Pad1U16)") (class "Default")
      (node (ref "U1") (pin "1U16") (pinfunction "HDMI_TX_REXT_1U16") (pintype "bidirectional+no_connect"))
    )
    (net (code "157") (name "unconnected-(U1B-ISP_FLASHTRIGOUT{slash}EBC_SDCE0{slash}GMAC1_TXEN_M1{slash}SPI3_CS0_M0{slash}I2S1_SCLK_RX_M1{slash}GPIO4_A6_D-PadAH2)") (class "Default")
      (node (ref "U1") (pin "AH2") (pinfunction "ISP_FLASHTRIGOUT/EBC_SDCE0/GMAC1_TXEN_M1/SPI3_CS0_M0/I2S1_SCLK_RX_M1/GPIO4_A6_D_AH2") (pintype "bidirectional+no_connect"))
    )
    (net (code "158") (name "unconnected-(U1B-ISP_PRELIGHT_TRIG{slash}EBC_SDCE3{slash}GMAC1_RXDV_CRS_M1{slash}I2S1_SDO2_M1{slash}GPIO4_B1_D-PadAG2)") (class "Default")
      (node (ref "U1") (pin "AG2") (pinfunction "ISP_PRELIGHT_TRIG/EBC_SDCE3/GMAC1_RXDV_CRS_M1/I2S1_SDO2_M1/GPIO4_B1_D_AG2") (pintype "bidirectional+no_connect"))
    )
    (net (code "159") (name "unconnected-(U1B-PCIE20_REFCLKN-Pad1K20)") (class "Default")
      (node (ref "U1") (pin "1K20") (pinfunction "PCIE20_REFCLKN_1K20") (pintype "bidirectional+no_connect"))
    )
    (net (code "160") (name "unconnected-(U1B-PCIE20_REFCLKP-Pad1K19)") (class "Default")
      (node (ref "U1") (pin "1K19") (pinfunction "PCIE20_REFCLKP_1K19") (pintype "bidirectional+no_connect"))
    )
    (net (code "161") (name "unconnected-(U1B-PCIE20_RXN{slash}SATA2_RXN-PadAB38)") (class "Default")
      (node (ref "U1") (pin "AB38") (pinfunction "PCIE20_RXN/SATA2_RXN_AB38") (pintype "input+no_connect"))
    )
    (net (code "162") (name "unconnected-(U1B-PCIE20_RXP{slash}SATA2_RXP-PadAB37)") (class "Default")
      (node (ref "U1") (pin "AB37") (pinfunction "PCIE20_RXP/SATA2_RXP_AB37") (pintype "input+no_connect"))
    )
    (net (code "163") (name "unconnected-(U1B-PCIE20_TXN{slash}SATA2_TXN-PadAA38)") (class "Default")
      (node (ref "U1") (pin "AA38") (pinfunction "PCIE20_TXN/SATA2_TXN_AA38") (pintype "output+no_connect"))
    )
    (net (code "164") (name "unconnected-(U1B-PCIE20_TXP{slash}SATA2_TXP-PadAA37)") (class "Default")
      (node (ref "U1") (pin "AA37") (pinfunction "PCIE20_TXP/SATA2_TXP_AA37") (pintype "output+no_connect"))
    )
    (net (code "165") (name "unconnected-(U1B-PWM0_M0{slash}CPUAVS{slash}GPIO0_B7_D-Pad1R17)") (class "Default")
      (node (ref "U1") (pin "1R17") (pinfunction "PWM0_M0/CPUAVS/GPIO0_B7_D_1R17") (pintype "bidirectional+no_connect"))
    )
    (net (code "166") (name "unconnected-(U1B-PWM1_M0{slash}GPUAVS{slash}UART0_RX{slash}GPIO0_C0_D-Pad1T19)") (class "Default")
      (node (ref "U1") (pin "1T19") (pinfunction "PWM1_M0/GPUAVS/UART0_RX/GPIO0_C0_D_1T19") (pintype "bidirectional+no_connect"))
    )
    (net (code "167") (name "unconnected-(U1B-PWM2_M0{slash}NPUAVS{slash}UART0_TX{slash}MCU_JTAG_TDI{slash}GPIO0_C1_D-Pad1R18)") (class "Default")
      (node (ref "U1") (pin "1R18") (pinfunction "PWM2_M0/NPUAVS/UART0_TX/MCU_JTAG_TDI/GPIO0_C1_D_1R18") (pintype "bidirectional+no_connect"))
    )
    (net (code "168") (name "unconnected-(U1B-PWM3_IR{slash}EDP_HPDIN_M1{slash}MCU_JTAG_TMS{slash}GPIO0_C2_D-PadAM37)") (class "Default")
      (node (ref "U1") (pin "AM37") (pinfunction "PWM3_IR/EDP_HPDIN_M1/MCU_JTAG_TMS/GPIO0_C2_D_AM37") (pintype "bidirectional+no_connect"))
    )
    (net (code "169") (name "unconnected-(U1B-PWM4{slash}VOP_PWM_M0{slash}MCU_JTAG_~{TRST}{slash}GPIO0_C3_D-PadAN38)") (class "Default")
      (node (ref "U1") (pin "AN38") (pinfunction "PWM4/VOP_PWM_M0/MCU_JTAG_~{TRST}/GPIO0_C3_D_AN38") (pintype "bidirectional+no_connect"))
    )
    (net (code "170") (name "unconnected-(U1B-PWM5{slash}SPI0_CS1_M0{slash}UART0_~{RTS}{slash}GPIO0_C4_D-PadAN37)") (class "Default")
      (node (ref "U1") (pin "AN37") (pinfunction "PWM5/SPI0_CS1_M0/UART0_~{RTS}/GPIO0_C4_D_AN37") (pintype "bidirectional+no_connect"))
    )
    (net (code "171") (name "unconnected-(U1B-PWM6{slash}SPI0_MISO_M0{slash}GPIO0_C5_D-Pad1U19)") (class "Default")
      (node (ref "U1") (pin "1U19") (pinfunction "PWM6/SPI0_MISO_M0/GPIO0_C5_D_1U19") (pintype "bidirectional+no_connect"))
    )
    (net (code "172") (name "unconnected-(U1B-PWM7_IR{slash}SPI0_CS0_M0{slash}GPIO0_C6_D-Pad1T18)") (class "Default")
      (node (ref "U1") (pin "1T18") (pinfunction "PWM7_IR/SPI0_CS0_M0/GPIO0_C6_D_1T18") (pintype "bidirectional+no_connect"))
    )
    (net (code "173") (name "unconnected-(U1B-PWM12_M0{slash}GMAC1_TXEN_M0{slash}UART3_TX_M1{slash}PDM_SDI2_M2{slash}GPIO3_B7_D-PadAP5)") (class "Default")
      (node (ref "U1") (pin "AP5") (pinfunction "PWM12_M0/GMAC1_TXEN_M0/UART3_TX_M1/PDM_SDI2_M2/GPIO3_B7_D_AP5") (pintype "bidirectional+no_connect"))
    )
    (net (code "174") (name "unconnected-(U1B-PWM12_M1{slash}SPI3_MISO_M1{slash}SATA1_ACT_LED{slash}UART9_TX_M1{slash}I2S3_SDO_M1{slash}GPIO4_C5_D-Pad1U6)") (class "Default")
      (node (ref "U1") (pin "1U6") (pinfunction "PWM12_M1/SPI3_MISO_M1/SATA1_ACT_LED/UART9_TX_M1/I2S3_SDO_M1/GPIO4_C5_D_1U6") (pintype "bidirectional+no_connect"))
    )
    (net (code "175") (name "unconnected-(U1B-PWM13_M0{slash}GMAC1_MCLKINOUT_M0{slash}UART3_RX_M1{slash}PDM_SDI3_M2{slash}GPIO3_C0_D-PadAR4)") (class "Default")
      (node (ref "U1") (pin "AR4") (pinfunction "PWM13_M0/GMAC1_MCLKINOUT_M0/UART3_RX_M1/PDM_SDI3_M2/GPIO3_C0_D_AR4") (pintype "bidirectional+no_connect"))
    )
    (net (code "176") (name "unconnected-(U1B-PWM13_M1{slash}SPI3_CS0_M1{slash}SATA0_ACT_LED{slash}UART9_RX_M1{slash}I2S3_SDI_M1{slash}GPIO4_C6_D-Pad1T6)") (class "Default")
      (node (ref "U1") (pin "1T6") (pinfunction "PWM13_M1/SPI3_CS0_M1/SATA0_ACT_LED/UART9_RX_M1/I2S3_SDI_M1/GPIO4_C6_D_1T6") (pintype "bidirectional+no_connect"))
    )
    (net (code "177") (name "unconnected-(U1B-PWM14_M0{slash}VOP_PWM_M1{slash}GMAC1_MDC_M0{slash}UART7_TX_M1{slash}PDM_CLK1_M2{slash}GPIO3_C4_D-Pad1P3)") (class "Default")
      (node (ref "U1") (pin "1P3") (pinfunction "PWM14_M0/VOP_PWM_M1/GMAC1_MDC_M0/UART7_TX_M1/PDM_CLK1_M2/GPIO3_C4_D_1P3") (pintype "bidirectional+no_connect"))
    )
    (net (code "178") (name "unconnected-(U1B-PWM14_M1{slash}SPI3_CLK_M1{slash}I2S3_MCLK_M1{slash}GPIO4_C2_D-Pad1U7)") (class "Default")
      (node (ref "U1") (pin "1U7") (pinfunction "PWM14_M1/SPI3_CLK_M1/I2S3_MCLK_M1/GPIO4_C2_D_1U7") (pintype "bidirectional+no_connect"))
    )
    (net (code "179") (name "unconnected-(U1B-PWM15_IR_M0{slash}SPDIF_TX_M1{slash}GMAC1_MDIO_M0{slash}UART7_RX_M1{slash}I2S1_LRCK_RX_M2{slash}GPIO3_C5_D-Pad1P4)") (class "Default")
      (node (ref "U1") (pin "1P4") (pinfunction "PWM15_IR_M0/SPDIF_TX_M1/GMAC1_MDIO_M0/UART7_RX_M1/I2S1_LRCK_RX_M2/GPIO3_C5_D_1P4") (pintype "bidirectional+no_connect"))
    )
    (net (code "180") (name "unconnected-(U1B-PWM15_IR_M1{slash}SPI3_MOSI_M1{slash}I2S3_SCLK_M1{slash}GPIO4_C3_D-PadAP12)") (class "Default")
      (node (ref "U1") (pin "AP12") (pinfunction "PWM15_IR_M1/SPI3_MOSI_M1/I2S3_SCLK_M1/GPIO4_C3_D_AP12") (pintype "bidirectional+no_connect"))
    )
    (net (code "181") (name "unconnected-(U1B-USB3_HOST1_DM-Pad1J20)") (class "Default")
      (node (ref "U1") (pin "1J20") (pinfunction "USB3_HOST1_DM_1J20") (pintype "bidirectional+no_connect"))
    )
    (net (code "182") (name "unconnected-(U1B-USB3_HOST1_DP-Pad1J19)") (class "Default")
      (node (ref "U1") (pin "1J19") (pinfunction "USB3_HOST1_DP_1J19") (pintype "bidirectional+no_connect"))
    )
    (net (code "183") (name "unconnected-(U1B-USB3_HOST1_SSRXN{slash}SATA1_RXN-PadV37)") (class "Default")
      (node (ref "U1") (pin "V37") (pinfunction "USB3_HOST1_SSRXN/SATA1_RXN_V37") (pintype "input+no_connect"))
    )
    (net (code "184") (name "unconnected-(U1B-USB3_HOST1_SSRXP{slash}SATA1_RXP-PadV38)") (class "Default")
      (node (ref "U1") (pin "V38") (pinfunction "USB3_HOST1_SSRXP/SATA1_RXP_V38") (pintype "input+no_connect"))
    )
    (net (code "185") (name "unconnected-(U1B-USB3_HOST1_SSTXN{slash}SATA1_TXN-PadW38)") (class "Default")
      (node (ref "U1") (pin "W38") (pinfunction "USB3_HOST1_SSTXN/SATA1_TXN_W38") (pintype "output+no_connect"))
    )
    (net (code "186") (name "unconnected-(U1B-USB3_HOST1_SSTXP{slash}SATA1_TXP-PadW37)") (class "Default")
      (node (ref "U1") (pin "W37") (pinfunction "USB3_HOST1_SSTXP/SATA1_TXP_W37") (pintype "output+no_connect"))
    )
    (net (code "187") (name "unconnected-(U1B-USB_HOST2_DM-PadV1)") (class "Default")
      (node (ref "U1") (pin "V1") (pinfunction "USB_HOST2_DM_V1") (pintype "bidirectional+no_connect"))
    )
    (net (code "188") (name "unconnected-(U1B-USB_HOST2_DP-PadV2)") (class "Default")
      (node (ref "U1") (pin "V2") (pinfunction "USB_HOST2_DP_V2") (pintype "bidirectional+no_connect"))
    )
    (net (code "189") (name "unconnected-(U1B-USB_HOST3_DM-PadY1)") (class "Default")
      (node (ref "U1") (pin "Y1") (pinfunction "USB_HOST3_DM_Y1") (pintype "bidirectional+no_connect"))
    )
    (net (code "190") (name "unconnected-(U1B-USB_HOST3_DP-PadY2)") (class "Default")
      (node (ref "U1") (pin "Y2") (pinfunction "USB_HOST3_DP_Y2") (pintype "bidirectional+no_connect"))
    )
    (net (code "191") (name "unconnected-(U1B-USB_OTG0_ID-PadT37)") (class "Default")
      (node (ref "U1") (pin "T37") (pinfunction "USB_OTG0_ID_T37") (pintype "input+no_connect"))
    )
    (net (code "192") (name "unconnected-(U1B-USB_OTG0_VBUSDET-PadT38)") (class "Default")
      (node (ref "U1") (pin "T38") (pinfunction "USB_OTG0_VBUSDET_T38") (pintype "input+no_connect"))
    )
    (net (code "193") (name "unconnected-(U1B-XIN24M-PadAD37)") (class "Default")
      (node (ref "U1") (pin "AD37") (pinfunction "XIN24M_AD37") (pintype "input+no_connect"))
    )
    (net (code "194") (name "unconnected-(U1B-XOUT24M-PadAD38)") (class "Default")
      (node (ref "U1") (pin "AD38") (pinfunction "XOUT24M_AD38") (pintype "output+no_connect"))
    )
    (net (code "195") (name "unconnected-(U1C-CIF_CLKIN{slash}EBC_SDCLK{slash}GMAC1_MCLKINOUT_M1{slash}UART1_~{CTS}_M1{slash}I2S2_SCLK_RX_M1{slash}GPIO4_C1_D-PadAB1)") (class "Default")
      (node (ref "U1") (pin "AB1") (pinfunction "CIF_CLKIN/EBC_SDCLK/GMAC1_MCLKINOUT_M1/UART1_~{CTS}_M1/I2S2_SCLK_RX_M1/GPIO4_C1_D_AB1") (pintype "bidirectional+no_connect"))
    )
    (net (code "196") (name "unconnected-(U1C-CIF_CLKOUT{slash}EBC_GDCLK{slash}PWM11_IR_M1{slash}GPIO4_C0_D-PadAB2)") (class "Default")
      (node (ref "U1") (pin "AB2") (pinfunction "CIF_CLKOUT/EBC_GDCLK/PWM11_IR_M1/GPIO4_C0_D_AB2") (pintype "bidirectional+no_connect"))
    )
    (net (code "197") (name "unconnected-(U1C-CIF_D0{slash}EBC_SDDO0{slash}SDMMC2_D0_M0{slash}I2S1_MCLK_M1{slash}VOP_BT656_D0_M1{slash}GPIO3_C6_D-Pad1T2)") (class "Default")
      (node (ref "U1") (pin "1T2") (pinfunction "CIF_D0/EBC_SDDO0/SDMMC2_D0_M0/I2S1_MCLK_M1/VOP_BT656_D0_M1/GPIO3_C6_D_1T2") (pintype "bidirectional+no_connect"))
    )
    (net (code "198") (name "unconnected-(U1C-CIF_D1{slash}EBC_SDDO1{slash}SDMMC2_D1_M0{slash}I2S1_SCLK_TX_M1{slash}VOP_BT656_D1_M1{slash}GPIO3_C7_D-Pad1U1)") (class "Default")
      (node (ref "U1") (pin "1U1") (pinfunction "CIF_D1/EBC_SDDO1/SDMMC2_D1_M0/I2S1_SCLK_TX_M1/VOP_BT656_D1_M1/GPIO3_C7_D_1U1") (pintype "bidirectional+no_connect"))
    )
    (net (code "199") (name "unconnected-(U1C-CIF_D2{slash}EBC_SDDO2{slash}SDMMC2_D2_M0{slash}I2S1_LRCK_TX_M1{slash}VOP_BT656_D2_M1{slash}GPIO3_D0_D-PadAP1)") (class "Default")
      (node (ref "U1") (pin "AP1") (pinfunction "CIF_D2/EBC_SDDO2/SDMMC2_D2_M0/I2S1_LRCK_TX_M1/VOP_BT656_D2_M1/GPIO3_D0_D_AP1") (pintype "bidirectional+no_connect"))
    )
    (net (code "200") (name "unconnected-(U1C-CIF_D3{slash}EBC_SDDO3{slash}SDMMC2_D3_M0{slash}I2S1_SDO0_M1{slash}VOP_BT656_D3_M1{slash}GPIO3_D1_D-PadAN2)") (class "Default")
      (node (ref "U1") (pin "AN2") (pinfunction "CIF_D3/EBC_SDDO3/SDMMC2_D3_M0/I2S1_SDO0_M1/VOP_BT656_D3_M1/GPIO3_D1_D_AN2") (pintype "bidirectional+no_connect"))
    )
    (net (code "201") (name "unconnected-(U1C-CIF_D4{slash}EBC_SDDO4{slash}SDMMC2_CMD_M0{slash}I2S1_SDI0_M1{slash}VOP_BT656_D4_M1{slash}GPIO3_D2_D-PadAM2)") (class "Default")
      (node (ref "U1") (pin "AM2") (pinfunction "CIF_D4/EBC_SDDO4/SDMMC2_CMD_M0/I2S1_SDI0_M1/VOP_BT656_D4_M1/GPIO3_D2_D_AM2") (pintype "bidirectional+no_connect"))
    )
    (net (code "202") (name "unconnected-(U1C-CIF_D5{slash}EBC_SDDO5{slash}SDMMC2_CLK_M0{slash}I2S1_SDI1_M1{slash}VOP_BT656_D5_M1{slash}GPIO3_D3_D-PadAM1)") (class "Default")
      (node (ref "U1") (pin "AM1") (pinfunction "CIF_D5/EBC_SDDO5/SDMMC2_CLK_M0/I2S1_SDI1_M1/VOP_BT656_D5_M1/GPIO3_D3_D_AM1") (pintype "bidirectional+no_connect"))
    )
    (net (code "203") (name "unconnected-(U1C-CIF_D6{slash}EBC_SDDO6{slash}SDMMC2_DET_M0{slash}I2S1_SDI2_M1{slash}VOP_BT656_D6_M1{slash}GPIO3_D4_D-Pad1R2)") (class "Default")
      (node (ref "U1") (pin "1R2") (pinfunction "CIF_D6/EBC_SDDO6/SDMMC2_DET_M0/I2S1_SDI2_M1/VOP_BT656_D6_M1/GPIO3_D4_D_1R2") (pintype "bidirectional+no_connect"))
    )
    (net (code "204") (name "unconnected-(U1C-CIF_D7{slash}EBC_SDDO7{slash}SDMMC2_PWREN_M0{slash}I2S1_SDI3_M1{slash}VOP_BT656_D7_M1{slash}GPIO3_D5_D-Pad1T1)") (class "Default")
      (node (ref "U1") (pin "1T1") (pinfunction "CIF_D7/EBC_SDDO7/SDMMC2_PWREN_M0/I2S1_SDI3_M1/VOP_BT656_D7_M1/GPIO3_D5_D_1T1") (pintype "bidirectional+no_connect"))
    )
    (net (code "205") (name "unconnected-(U1C-CIF_D8{slash}EBC_SDDO8{slash}GMAC1_TXD2_M1{slash}UART1_TX_M1{slash}PDM_CLK0_M1{slash}GPIO3_D6_D-PadAL2)") (class "Default")
      (node (ref "U1") (pin "AL2") (pinfunction "CIF_D8/EBC_SDDO8/GMAC1_TXD2_M1/UART1_TX_M1/PDM_CLK0_M1/GPIO3_D6_D_AL2") (pintype "bidirectional+no_connect"))
    )
    (net (code "206") (name "unconnected-(U1C-CIF_D9{slash}EBC_SDDO9{slash}GMAC1_TXD3_M1{slash}UART1_RX_M1{slash}PDM_SDI0_M1{slash}GPIO3_D7_D-PadAL1)") (class "Default")
      (node (ref "U1") (pin "AL1") (pinfunction "CIF_D9/EBC_SDDO9/GMAC1_TXD3_M1/UART1_RX_M1/PDM_SDI0_M1/GPIO3_D7_D_AL1") (pintype "bidirectional+no_connect"))
    )
    (net (code "207") (name "unconnected-(U1C-CIF_D10{slash}EBC_SDDO10{slash}GMAC1_TXCLK_M1{slash}PDM_CLK1_M1{slash}GPIO4_A0_D-PadAK2)") (class "Default")
      (node (ref "U1") (pin "AK2") (pinfunction "CIF_D10/EBC_SDDO10/GMAC1_TXCLK_M1/PDM_CLK1_M1/GPIO4_A0_D_AK2") (pintype "bidirectional+no_connect"))
    )
    (net (code "208") (name "unconnected-(U1C-CIF_D11{slash}EBC_SDDO11{slash}GMAC1_RXD2_M1{slash}PDM_SDI1_M1{slash}GPIO4_A1_D-Pad1P2)") (class "Default")
      (node (ref "U1") (pin "1P2") (pinfunction "CIF_D11/EBC_SDDO11/GMAC1_RXD2_M1/PDM_SDI1_M1/GPIO4_A1_D_1P2") (pintype "bidirectional+no_connect"))
    )
    (net (code "209") (name "unconnected-(U1C-CIF_D12{slash}EBC_SDDO12{slash}GMAC1_RXD3_M1{slash}UART7_TX_M2{slash}PDM_SDI2_M1{slash}GPIO4_A2_D-Pad1R1)") (class "Default")
      (node (ref "U1") (pin "1R1") (pinfunction "CIF_D12/EBC_SDDO12/GMAC1_RXD3_M1/UART7_TX_M2/PDM_SDI2_M1/GPIO4_A2_D_1R1") (pintype "bidirectional+no_connect"))
    )
    (net (code "210") (name "unconnected-(U1C-CIF_D13{slash}EBC_SDDO13{slash}GMAC1_RXCLK_M1{slash}UART7_RX_M2{slash}PDM_SDI3_M1{slash}GPIO4_A3_D-PadAJ2)") (class "Default")
      (node (ref "U1") (pin "AJ2") (pinfunction "CIF_D13/EBC_SDDO13/GMAC1_RXCLK_M1/UART7_RX_M2/PDM_SDI3_M1/GPIO4_A3_D_AJ2") (pintype "bidirectional+no_connect"))
    )
    (net (code "211") (name "unconnected-(U1C-CIF_D14{slash}EBC_SDDO14{slash}GMAC1_TXD0_M1{slash}UART9_TX_M2{slash}I2S2_LRCK_TX_M1{slash}GPIO4_A4_D-Pad1N2)") (class "Default")
      (node (ref "U1") (pin "1N2") (pinfunction "CIF_D14/EBC_SDDO14/GMAC1_TXD0_M1/UART9_TX_M2/I2S2_LRCK_TX_M1/GPIO4_A4_D_1N2") (pintype "bidirectional+no_connect"))
    )
    (net (code "212") (name "unconnected-(U1C-CIF_D15{slash}EBC_SDDO15{slash}GMAC1_TXD1_M1{slash}UART9_RX_M2{slash}I2S2_LRCK_RX_M1{slash}GPIO4_A5_D-PadAJ1)") (class "Default")
      (node (ref "U1") (pin "AJ1") (pinfunction "CIF_D15/EBC_SDDO15/GMAC1_TXD1_M1/UART9_RX_M2/I2S2_LRCK_RX_M1/GPIO4_A5_D_AJ1") (pintype "bidirectional+no_connect"))
    )
    (net (code "213") (name "unconnected-(U1C-CIF_HREF{slash}EBC_SDLE{slash}GMAC1_MDC_M1{slash}UART1_~{RTS}_M1{slash}I2S2_MCLK_M1{slash}GPIO4_B6_D-Pad1L1)") (class "Default")
      (node (ref "U1") (pin "1L1") (pinfunction "CIF_HREF/EBC_SDLE/GMAC1_MDC_M1/UART1_~{RTS}_M1/I2S2_MCLK_M1/GPIO4_B6_D_1L1") (pintype "bidirectional+no_connect"))
    )
    (net (code "214") (name "unconnected-(U1C-CIF_VSYNC{slash}EBC_SDOE{slash}GMAC1_MDIO_M1{slash}I2S2_SCLK_TX_M1{slash}GPIO4_B7_D-PadAC2)") (class "Default")
      (node (ref "U1") (pin "AC2") (pinfunction "CIF_VSYNC/EBC_SDOE/GMAC1_MDIO_M1/I2S2_SCLK_TX_M1/GPIO4_B7_D_AC2") (pintype "bidirectional+no_connect"))
    )
    (net (code "215") (name "unconnected-(U1C-CLK32K_OUT1{slash}UART8_RX_M0{slash}SPI1_CS1_M0{slash}GPIO2_C6_D-PadB38)") (class "Default")
      (node (ref "U1") (pin "B38") (pinfunction "CLK32K_OUT1/UART8_RX_M0/SPI1_CS1_M0/GPIO2_C6_D_B38") (pintype "bidirectional+no_connect"))
    )
    (net (code "216") (name "unconnected-(U1C-EMMC_CLKOUT{slash}FLASH_DQS{slash}GPIO1_C5_D-PadA29)") (class "Default")
      (node (ref "U1") (pin "A29") (pinfunction "EMMC_CLKOUT/FLASH_DQS/GPIO1_C5_D_A29") (pintype "bidirectional+no_connect"))
    )
    (net (code "217") (name "unconnected-(U1C-EMMC_CMD{slash}FLASH_~{WR}{slash}GPIO1_C4_U-PadA27)") (class "Default")
      (node (ref "U1") (pin "A27") (pinfunction "EMMC_CMD/FLASH_~{WR}/GPIO1_C4_U_A27") (pintype "bidirectional+no_connect"))
    )
    (net (code "218") (name "unconnected-(U1C-EMMC_D0{slash}FLASH_D0{slash}GPIO1_B4_U-PadA32)") (class "Default")
      (node (ref "U1") (pin "A32") (pinfunction "EMMC_D0/FLASH_D0/GPIO1_B4_U_A32") (pintype "bidirectional+no_connect"))
    )
    (net (code "219") (name "unconnected-(U1C-EMMC_D1{slash}FLASH_D1{slash}GPIO1_B5_U-PadB27)") (class "Default")
      (node (ref "U1") (pin "B27") (pinfunction "EMMC_D1/FLASH_D1/GPIO1_B5_U_B27") (pintype "bidirectional+no_connect"))
    )
    (net (code "220") (name "unconnected-(U1C-EMMC_D2{slash}FLASH_D2{slash}GPIO1_B6_U-PadB32)") (class "Default")
      (node (ref "U1") (pin "B32") (pinfunction "EMMC_D2/FLASH_D2/GPIO1_B6_U_B32") (pintype "bidirectional+no_connect"))
    )
    (net (code "221") (name "unconnected-(U1C-EMMC_D3{slash}FLASH_D3{slash}GPIO1_B7_U-PadB29)") (class "Default")
      (node (ref "U1") (pin "B29") (pinfunction "EMMC_D3/FLASH_D3/GPIO1_B7_U_B29") (pintype "bidirectional+no_connect"))
    )
    (net (code "222") (name "unconnected-(U1C-EMMC_D4{slash}FLASH_D4{slash}GPIO1_C0_U-PadB33)") (class "Default")
      (node (ref "U1") (pin "B33") (pinfunction "EMMC_D4/FLASH_D4/GPIO1_C0_U_B33") (pintype "bidirectional+no_connect"))
    )
    (net (code "223") (name "unconnected-(U1C-EMMC_D5{slash}FLASH_D5{slash}GPIO1_C1_U-PadA30)") (class "Default")
      (node (ref "U1") (pin "A30") (pinfunction "EMMC_D5/FLASH_D5/GPIO1_C1_U_A30") (pintype "bidirectional+no_connect"))
    )
    (net (code "224") (name "unconnected-(U1C-EMMC_D6{slash}FLASH_D6{slash}GPIO1_C2_U-PadB30)") (class "Default")
      (node (ref "U1") (pin "B30") (pinfunction "EMMC_D6/FLASH_D6/GPIO1_C2_U_B30") (pintype "bidirectional+no_connect"))
    )
    (net (code "225") (name "unconnected-(U1C-EMMC_D7{slash}FLASH_D7{slash}GPIO1_C3_U-PadA33)") (class "Default")
      (node (ref "U1") (pin "A33") (pinfunction "EMMC_D7/FLASH_D7/GPIO1_C3_U_A33") (pintype "bidirectional+no_connect"))
    )
    (net (code "226") (name "unconnected-(U1C-EMMC_DATA_STROBE{slash}FSPI_~{CS1}{slash}FLASH_CLE{slash}GPIO1_C6_D-Pad1A16)") (class "Default")
      (node (ref "U1") (pin "1A16") (pinfunction "EMMC_DATA_STROBE/FSPI_~{CS1}/FLASH_CLE/GPIO1_C6_D_1A16") (pintype "bidirectional+no_connect"))
    )
    (net (code "227") (name "unconnected-(U1C-I2C0_SCL{slash}GPIO0_B1_U-PadAJ37)") (class "Default")
      (node (ref "U1") (pin "AJ37") (pinfunction "I2C0_SCL/GPIO0_B1_U_AJ37") (pintype "bidirectional+no_connect"))
    )
    (net (code "228") (name "unconnected-(U1C-I2C0_SDA{slash}GPIO0_B2_U-PadAK38)") (class "Default")
      (node (ref "U1") (pin "AK38") (pinfunction "I2C0_SDA/GPIO0_B2_U_AK38") (pintype "bidirectional+no_connect"))
    )
    (net (code "229") (name "unconnected-(U1C-I2C1_SCL{slash}MCU_JTAG_TDO{slash}GPIO0_B3_U-PadAK37)") (class "Default")
      (node (ref "U1") (pin "AK37") (pinfunction "I2C1_SCL/MCU_JTAG_TDO/GPIO0_B3_U_AK37") (pintype "bidirectional+no_connect"))
    )
    (net (code "230") (name "unconnected-(U1C-I2C1_SDA{slash}PCIE20_~{BUTTONRST}{slash}MCU_JTAG_TCK{slash}GPIO0_B4_U-PadAM38)") (class "Default")
      (node (ref "U1") (pin "AM38") (pinfunction "I2C1_SDA/PCIE20_~{BUTTONRST}/MCU_JTAG_TCK/GPIO0_B4_U_AM38") (pintype "bidirectional+no_connect"))
    )
    (net (code "231") (name "unconnected-(U1C-I2C2_SCL_M0{slash}SPI0_CLK_M0{slash}PCIE20_~{WAKE}_M0{slash}PWM1_M1{slash}GPIO0_B5_U-Pad1U20)") (class "Default")
      (node (ref "U1") (pin "1U20") (pinfunction "I2C2_SCL_M0/SPI0_CLK_M0/PCIE20_~{WAKE}_M0/PWM1_M1/GPIO0_B5_U_1U20") (pintype "bidirectional+no_connect"))
    )
    (net (code "232") (name "unconnected-(U1C-I2C2_SCL_M1{slash}EBC_SDSHR{slash}I2S1_SDO3_M1{slash}GPIO4_B5_D-PadAD1)") (class "Default")
      (node (ref "U1") (pin "AD1") (pinfunction "I2C2_SCL_M1/EBC_SDSHR/I2S1_SDO3_M1/GPIO4_B5_D_AD1") (pintype "bidirectional+no_connect"))
    )
    (net (code "233") (name "unconnected-(U1C-I2C2_SDA_M0{slash}SPI0_MOSI_M0{slash}PCIE20_~{PERST}_M0{slash}PWM2_M1{slash}GPIO0_B6_U-Pad1R16)") (class "Default")
      (node (ref "U1") (pin "1R16") (pinfunction "I2C2_SDA_M0/SPI0_MOSI_M0/PCIE20_~{PERST}_M0/PWM2_M1/GPIO0_B6_U_1R16") (pintype "bidirectional+no_connect"))
    )
    (net (code "234") (name "unconnected-(U1C-I2C2_SDA_M1{slash}EBC_GDSP{slash}ISP_FLASH_TRIGIN{slash}VOP_BT656_CLK_M1{slash}GPIO4_B4_D-PadAF1)") (class "Default")
      (node (ref "U1") (pin "AF1") (pinfunction "I2C2_SDA_M1/EBC_GDSP/ISP_FLASH_TRIGIN/VOP_BT656_CLK_M1/GPIO4_B4_D_AF1") (pintype "bidirectional+no_connect"))
    )
    (net (code "235") (name "unconnected-(U1C-I2C3_SCL_M0{slash}UART3_TX_M0{slash}AUDIOPWM_LOUT_N{slash}GPIO1_A1_U-PadB22)") (class "Default")
      (node (ref "U1") (pin "B22") (pinfunction "I2C3_SCL_M0/UART3_TX_M0/AUDIOPWM_LOUT_N/GPIO1_A1_U_B22") (pintype "bidirectional+no_connect"))
    )
    (net (code "236") (name "unconnected-(U1C-I2C3_SDA_M0{slash}UART3_RX_M0{slash}AUDIOPWM_LOUT_P{slash}GPIO1_A0_U-PadA22)") (class "Default")
      (node (ref "U1") (pin "A22") (pinfunction "I2C3_SDA_M0/UART3_RX_M0/AUDIOPWM_LOUT_P/GPIO1_A0_U_A22") (pintype "bidirectional+no_connect"))
    )
    (net (code "237") (name "unconnected-(U1C-I2C4_SCL_M0{slash}EBC_GDOE{slash}ETH1_REFCLKO_25M_M1{slash}SPI3_CLK_M0{slash}I2S2_SDO_M1{slash}GPIO4_B3_D-PadAE2)") (class "Default")
      (node (ref "U1") (pin "AE2") (pinfunction "I2C4_SCL_M0/EBC_GDOE/ETH1_REFCLKO_25M_M1/SPI3_CLK_M0/I2S2_SDO_M1/GPIO4_B3_D_AE2") (pintype "bidirectional+no_connect"))
    )
    (net (code "238") (name "unconnected-(U1C-I2C4_SDA_M0{slash}EBC_VCOM{slash}GMAC1_RXER_M1{slash}SPI3_MOSI_M0{slash}I2S2_SDI_M1{slash}GPIO4_B2_D-PadAF2)") (class "Default")
      (node (ref "U1") (pin "AF2") (pinfunction "I2C4_SDA_M0/EBC_VCOM/GMAC1_RXER_M1/SPI3_MOSI_M0/I2S2_SDI_M1/GPIO4_B2_D_AF2") (pintype "bidirectional+no_connect"))
    )
    (net (code "239") (name "unconnected-(U1C-I2S1_LRCK_RX_M0{slash}UART4_TX_M0{slash}PDM_CLK0_M0{slash}AUDIOPWM_ROUT_P{slash}GPIO1_A6_D-Pad1A14)") (class "Default")
      (node (ref "U1") (pin "1A14") (pinfunction "I2S1_LRCK_RX_M0/UART4_TX_M0/PDM_CLK0_M0/AUDIOPWM_ROUT_P/GPIO1_A6_D_1A14") (pintype "bidirectional+no_connect"))
    )
    (net (code "240") (name "unconnected-(U1C-I2S1_LRCK_TX_M0{slash}UART4_~{RTS}_M0{slash}SCR_RST{slash}GPIO1_A5_D-PadB24)") (class "Default")
      (node (ref "U1") (pin "B24") (pinfunction "I2S1_LRCK_TX_M0/UART4_~{RTS}_M0/SCR_RST/GPIO1_A5_D_B24") (pintype "bidirectional+no_connect"))
    )
    (net (code "241") (name "unconnected-(U1C-I2S1_MCLK_M0{slash}UART3_~{RTS}_M0{slash}SCR_CLK{slash}GPIO1_A2_D-PadA23)") (class "Default")
      (node (ref "U1") (pin "A23") (pinfunction "I2S1_MCLK_M0/UART3_~{RTS}_M0/SCR_CLK/GPIO1_A2_D_A23") (pintype "bidirectional+no_connect"))
    )
    (net (code "242") (name "unconnected-(U1C-I2S1_SCLK_RX_M0{slash}UART4_RX_M0{slash}PDM_CLK1_M0{slash}SPDIF_TX_M0{slash}GPIO1_A4_D-Pad1A13)") (class "Default")
      (node (ref "U1") (pin "1A13") (pinfunction "I2S1_SCLK_RX_M0/UART4_RX_M0/PDM_CLK1_M0/SPDIF_TX_M0/GPIO1_A4_D_1A13") (pintype "bidirectional+no_connect"))
    )
    (net (code "243") (name "unconnected-(U1C-I2S1_SCLK_TX_M0{slash}UART3_~{CTS}_M0{slash}SCR_IO{slash}GPIO1_A3_D-PadB23)") (class "Default")
      (node (ref "U1") (pin "B23") (pinfunction "I2S1_SCLK_TX_M0/UART3_~{CTS}_M0/SCR_IO/GPIO1_A3_D_B23") (pintype "bidirectional+no_connect"))
    )
    (net (code "244") (name "unconnected-(U1C-I2S1_SDI0_M0{slash}PDM_SDI0_M0{slash}GPIO1_B3_D-Pad1B14)") (class "Default")
      (node (ref "U1") (pin "1B14") (pinfunction "I2S1_SDI0_M0/PDM_SDI0_M0/GPIO1_B3_D_1B14") (pintype "bidirectional+no_connect"))
    )
    (net (code "245") (name "unconnected-(U1C-I2S1_SDO0_M0{slash}UART4_~{CTS}_M0{slash}SCR_DET{slash}AUDIOPWM_ROUT_N{slash}GPIO1_A7_D-PadB25)") (class "Default")
      (node (ref "U1") (pin "B25") (pinfunction "I2S1_SDO0_M0/UART4_~{CTS}_M0/SCR_DET/AUDIOPWM_ROUT_N/GPIO1_A7_D_B25") (pintype "bidirectional+no_connect"))
    )
    (net (code "246") (name "unconnected-(U1C-I2S1_SDO1_M0{slash}I2S1_SDI3_M0{slash}PDM_SDI3_M0{slash}PCIE20_~{CLKREQ}_M2{slash}GPIO1_B0_D-Pad1B13)") (class "Default")
      (node (ref "U1") (pin "1B13") (pinfunction "I2S1_SDO1_M0/I2S1_SDI3_M0/PDM_SDI3_M0/PCIE20_~{CLKREQ}_M2/GPIO1_B0_D_1B13") (pintype "bidirectional+no_connect"))
    )
    (net (code "247") (name "unconnected-(U1C-I2S1_SDO2_M0{slash}I2S1_SDI2_M0{slash}PDM_SDI2_M0{slash}PCIE20_~{WAKE}_M2{slash}GPIO1_B1_D-PadA26)") (class "Default")
      (node (ref "U1") (pin "A26") (pinfunction "I2S1_SDO2_M0/I2S1_SDI2_M0/PDM_SDI2_M0/PCIE20_~{WAKE}_M2/GPIO1_B1_D_A26") (pintype "bidirectional+no_connect"))
    )
    (net (code "248") (name "unconnected-(U1C-I2S1_SDO3_M0{slash}I2S1_SDI1_M0{slash}PDM_SDI1_M0{slash}PCIE20_~{PERST}_M2{slash}GPIO1_B2_D-PadB26)") (class "Default")
      (node (ref "U1") (pin "B26") (pinfunction "I2S1_SDO3_M0/I2S1_SDI1_M0/PDM_SDI1_M0/PCIE20_~{PERST}_M2/GPIO1_B2_D_B26") (pintype "bidirectional+no_connect"))
    )
    (net (code "249") (name "unconnected-(U1C-I2S2_LRCK_RX_M0{slash}UART6_~{CTS}_M0{slash}SPI1_CS0_M0{slash}GPIO2_C0_D-PadA37)") (class "Default")
      (node (ref "U1") (pin "A37") (pinfunction "I2S2_LRCK_RX_M0/UART6_~{CTS}_M0/SPI1_CS0_M0/GPIO2_C0_D_A37") (pintype "bidirectional+no_connect"))
    )
    (net (code "250") (name "unconnected-(U1C-I2S2_LRCK_TX_M0{slash}UART9_~{RTS}_M0{slash}SPI2_MOSI_M0{slash}GPIO2_C3_D-Pad1D19)") (class "Default")
      (node (ref "U1") (pin "1D19") (pinfunction "I2S2_LRCK_TX_M0/UART9_~{RTS}_M0/SPI2_MOSI_M0/GPIO2_C3_D_1D19") (pintype "bidirectional+no_connect"))
    )
    (net (code "251") (name "unconnected-(U1C-I2S2_MCLK_M0{slash}ETH0_REFCLKO_25M{slash}UART7_~{RTS}_M0{slash}SPI2_CLK_M0{slash}GPIO2_C1_D-PadB36)") (class "Default")
      (node (ref "U1") (pin "B36") (pinfunction "I2S2_MCLK_M0/ETH0_REFCLKO_25M/UART7_~{RTS}_M0/SPI2_CLK_M0/GPIO2_C1_D_B36") (pintype "bidirectional+no_connect"))
    )
    (net (code "252") (name "unconnected-(U1C-I2S2_SCLK_RX_M0{slash}UART6_~{RTS}_M0{slash}SPI1_MOSI_M0{slash}GPIO2_B7_D-PadD38)") (class "Default")
      (node (ref "U1") (pin "D38") (pinfunction "I2S2_SCLK_RX_M0/UART6_~{RTS}_M0/SPI1_MOSI_M0/GPIO2_B7_D_D38") (pintype "bidirectional+no_connect"))
    )
    (net (code "253") (name "unconnected-(U1C-I2S2_SCLK_TX_M0{slash}UART7_~{CTS}_M0{slash}SPI2_MISO_M0{slash}GPIO2_C2_D-PadC37)") (class "Default")
      (node (ref "U1") (pin "C37") (pinfunction "I2S2_SCLK_TX_M0/UART7_~{CTS}_M0/SPI2_MISO_M0/GPIO2_C2_D_C37") (pintype "bidirectional+no_connect"))
    )
    (net (code "254") (name "unconnected-(U1C-I2S2_SDI_M0{slash}UART8_TX_M0{slash}SPI2_CS1_M0{slash}GPIO2_C5_D-PadD37)") (class "Default")
      (node (ref "U1") (pin "D37") (pinfunction "I2S2_SDI_M0/UART8_TX_M0/SPI2_CS1_M0/GPIO2_C5_D_D37") (pintype "bidirectional+no_connect"))
    )
    (net (code "255") (name "unconnected-(U1C-I2S2_SDO_M0{slash}UART9_~{CTS}_M0{slash}SPI2_CS0_M0{slash}GPIO2_C4_D-Pad1B20)") (class "Default")
      (node (ref "U1") (pin "1B20") (pinfunction "I2S2_SDO_M0/UART9_~{CTS}_M0/SPI2_CS0_M0/GPIO2_C4_D_1B20") (pintype "bidirectional+no_connect"))
    )
    (net (code "256") (name "unconnected-(U1C-~{RST}{slash}~{FSPI}_~{D}2{slash}~{FLASH}_~{WP}{slash}~{GPIO}1_~{C}7_~{D}-Pad1B16)") (class "Default")
      (node (ref "U1") (pin "1B16") (pinfunction "~{RST}/~{FSPI}_~{D}2/~{FLASH}_~{WP}/~{GPIO}1_~{C}7_~{D}_1B16") (pintype "bidirectional+no_connect"))
    )
    (net (code "257") (name "unconnected-(U1D-SDMMC0_PWREN{slash}SATA_MP_SWITCH{slash}PCIE20_~{CLKREQ}_M0{slash}GPIO0_A5_D-PadAG37)") (class "Default")
      (node (ref "U1") (pin "AG37") (pinfunction "SDMMC0_PWREN/SATA_MP_SWITCH/PCIE20_~{CLKREQ}_M0/GPIO0_A5_D_AG37") (pintype "bidirectional+no_connect"))
    )
    (net (code "258") (name "unconnected-(U1D-SDMMC1_CLK{slash}UART9_TX_M0{slash}GPIO2_B0_D-PadB37)") (class "Default")
      (node (ref "U1") (pin "B37") (pinfunction "SDMMC1_CLK/UART9_TX_M0/GPIO2_B0_D_B37") (pintype "bidirectional"))
    )
    (net (code "259") (name "unconnected-(U1D-SDMMC1_CMD{slash}UART9_RX_M0{slash}GPIO2_A7_U-PadB35)") (class "Default")
      (node (ref "U1") (pin "B35") (pinfunction "SDMMC1_CMD/UART9_RX_M0/GPIO2_A7_U_B35") (pintype "bidirectional"))
    )
    (net (code "260") (name "unconnected-(U1D-SDMMC1_D0{slash}UART6_RX_M0{slash}GPIO2_A3_U-Pad1C19)") (class "Default")
      (node (ref "U1") (pin "1C19") (pinfunction "SDMMC1_D0/UART6_RX_M0/GPIO2_A3_U_1C19") (pintype "bidirectional+no_connect"))
    )
    (net (code "261") (name "unconnected-(U1D-SDMMC1_D3{slash}UART7_TX_M0{slash}GPIO2_A6_U-Pad1A20)") (class "Default")
      (node (ref "U1") (pin "1A20") (pinfunction "SDMMC1_D3/UART7_TX_M0/GPIO2_A6_U_1A20") (pintype "bidirectional"))
    )
    (net (code "262") (name "unconnected-(U1D-SDMMC1_DET{slash}I2C4_SCL_M1{slash}UART8_~{CTS}_M0{slash}GPIO2_B2_U-PadB34)") (class "Default")
      (node (ref "U1") (pin "B34") (pinfunction "SDMMC1_DET/I2C4_SCL_M1/UART8_~{CTS}_M0/GPIO2_B2_U_B34") (pintype "bidirectional"))
    )
    (net (code "263") (name "unconnected-(U1D-SDMMC1_PWREN{slash}I2C4_SDA_M1{slash}UART8_~{RTS}_M0{slash}GPIO2_B1_D-PadA35)") (class "Default")
      (node (ref "U1") (pin "A35") (pinfunction "SDMMC1_PWREN/I2C4_SDA_M1/UART8_~{RTS}_M0/GPIO2_B1_D_A35") (pintype "bidirectional+no_connect"))
    )
    (net (code "264") (name "unconnected-(U1D-UART1_RX_M0{slash}GPIO2_B3_U-Pad1C20)") (class "Default")
      (node (ref "U1") (pin "1C20") (pinfunction "UART1_RX_M0/GPIO2_B3_U_1C20") (pintype "bidirectional+no_connect"))
    )
    (net (code "265") (name "unconnected-(U1D-UART1_TX_M0{slash}GPIO2_B4_U-PadF38)") (class "Default")
      (node (ref "U1") (pin "F38") (pinfunction "UART1_TX_M0/GPIO2_B4_U_F38") (pintype "bidirectional+no_connect"))
    )
    (net (code "266") (name "unconnected-(U1D-UART1_~{CTS}_M0{slash}SPI1_MISO_M0{slash}GPIO2_B6_U-PadG37)") (class "Default")
      (node (ref "U1") (pin "G37") (pinfunction "UART1_~{CTS}_M0/SPI1_MISO_M0/GPIO2_B6_U_G37") (pintype "bidirectional+no_connect"))
    )
    (net (code "267") (name "unconnected-(U1D-UART1_~{RTS}_M0{slash}SPI1_CLK_M0{slash}GPIO2_B5_U-PadF37)") (class "Default")
      (node (ref "U1") (pin "F37") (pinfunction "UART1_~{RTS}_M0/SPI1_CLK_M0/GPIO2_B5_U_F37") (pintype "bidirectional+no_connect"))
    )
    (net (code "268") (name "unconnected-(U1D-UART2_RX_M0{slash}GPIO0_D0_U-Pad1V19)") (class "Default")
      (node (ref "U1") (pin "1V19") (pinfunction "UART2_RX_M0/GPIO0_D0_U_1V19") (pintype "bidirectional+no_connect"))
    )
    (net (code "269") (name "unconnected-(U1D-UART2_TX_M0{slash}GPIO0_D1_U-Pad1U18)") (class "Default")
      (node (ref "U1") (pin "1U18") (pinfunction "UART2_TX_M0/GPIO0_D1_U_1U18") (pintype "bidirectional+no_connect"))
    )
    (net (code "270") (name "unconnected-(U1D-VOP_BT1120_CLK{slash}GMAC1_TXCLK_M0{slash}I2S3_SDI_M0{slash}SDMMC2_CLK_M1{slash}GPIO3_A6_D-Pad1U4)") (class "Default")
      (node (ref "U1") (pin "1U4") (pinfunction "VOP_BT1120_CLK/GMAC1_TXCLK_M0/I2S3_SDI_M0/SDMMC2_CLK_M1/GPIO3_A6_D_1U4") (pintype "bidirectional+no_connect"))
    )
    (net (code "271") (name "unconnected-(U1D-VOP_BT1120_D0{slash}SPI1_CS0_M1{slash}SDMMC2_D0_M1{slash}GPIO3_A1_D-Pad1U5)") (class "Default")
      (node (ref "U1") (pin "1U5") (pinfunction "VOP_BT1120_D0/SPI1_CS0_M1/SDMMC2_D0_M1/GPIO3_A1_D_1U5") (pintype "bidirectional+no_connect"))
    )
    (net (code "272") (name "unconnected-(U1D-VOP_BT1120_D1{slash}GMAC1_TXD2_M0{slash}I2S3_MCLK_M0{slash}SDMMC2_D1_M1{slash}GPIO3_A2_D-PadAR10)") (class "Default")
      (node (ref "U1") (pin "AR10") (pinfunction "VOP_BT1120_D1/GMAC1_TXD2_M0/I2S3_MCLK_M0/SDMMC2_D1_M1/GPIO3_A2_D_AR10") (pintype "bidirectional+no_connect"))
    )
    (net (code "273") (name "unconnected-(U1D-VOP_BT1120_D2{slash}GMAC1_TXD3_M0{slash}I2S3_SCLK_M0{slash}SDMMC2_D2_M1{slash}GPIO3_A3_D-PadAP10)") (class "Default")
      (node (ref "U1") (pin "AP10") (pinfunction "VOP_BT1120_D2/GMAC1_TXD3_M0/I2S3_SCLK_M0/SDMMC2_D2_M1/GPIO3_A3_D_AP10") (pintype "bidirectional+no_connect"))
    )
    (net (code "274") (name "unconnected-(U1D-VOP_BT1120_D3{slash}GMAC1_RXD2_M0{slash}I2S3_LRCK_M0{slash}SDMMC2_D3_M1{slash}GPIO3_A4_D-PadAR9)") (class "Default")
      (node (ref "U1") (pin "AR9") (pinfunction "VOP_BT1120_D3/GMAC1_RXD2_M0/I2S3_LRCK_M0/SDMMC2_D3_M1/GPIO3_A4_D_AR9") (pintype "bidirectional+no_connect"))
    )
    (net (code "275") (name "unconnected-(U1D-VOP_BT1120_D4{slash}GMAC1_RXD3_M0{slash}I2S3_SDO_M0{slash}SDMMC2_CMD_M1{slash}GPIO3_A5_D-PadAP9)") (class "Default")
      (node (ref "U1") (pin "AP9") (pinfunction "VOP_BT1120_D4/GMAC1_RXD3_M0/I2S3_SDO_M0/SDMMC2_CMD_M1/GPIO3_A5_D_AP9") (pintype "bidirectional+no_connect"))
    )
    (net (code "276") (name "unconnected-(U1D-VOP_BT1120_D5{slash}GMAC1_RXCLK_M0{slash}SDMMC2_DET_M1{slash}GPIO3_A7_D-Pad1V3)") (class "Default")
      (node (ref "U1") (pin "1V3") (pinfunction "VOP_BT1120_D5/GMAC1_RXCLK_M0/SDMMC2_DET_M1/GPIO3_A7_D_1V3") (pintype "bidirectional+no_connect"))
    )
    (net (code "277") (name "unconnected-(U1D-VOP_BT1120_D6{slash}ETH1_REFCLKO_25M_M0{slash}SDMMC2_PWREN_M1{slash}GPIO3_B0_D-PadAR7)") (class "Default")
      (node (ref "U1") (pin "AR7") (pinfunction "VOP_BT1120_D6/ETH1_REFCLKO_25M_M0/SDMMC2_PWREN_M1/GPIO3_B0_D_AR7") (pintype "bidirectional+no_connect"))
    )
    (net (code "278") (name "unconnected-(U1D-VOP_BT1120_D7{slash}GMAC1_RXD0_M0{slash}UART4_RX_M1{slash}PWM8_M0{slash}GPIO3_B1_D-PadAP7)") (class "Default")
      (node (ref "U1") (pin "AP7") (pinfunction "VOP_BT1120_D7/GMAC1_RXD0_M0/UART4_RX_M1/PWM8_M0/GPIO3_B1_D_AP7") (pintype "bidirectional+no_connect"))
    )
    (net (code "279") (name "unconnected-(U1D-VOP_BT1120_D8{slash}GMAC1_RXD1_M0{slash}UART4_TX_M1{slash}PWM9_M0{slash}GPIO3_B2_D-PadAR6)") (class "Default")
      (node (ref "U1") (pin "AR6") (pinfunction "VOP_BT1120_D8/GMAC1_RXD1_M0/UART4_TX_M1/PWM9_M0/GPIO3_B2_D_AR6") (pintype "bidirectional+no_connect"))
    )
    (net (code "280") (name "unconnected-(U1D-VOP_BT1120_D9{slash}GMAC1_RXDV_CRS_M0{slash}I2C5_SCL_M0{slash}PDM_SDI0_M2{slash}GPIO3_B3_D-PadAP6)") (class "Default")
      (node (ref "U1") (pin "AP6") (pinfunction "VOP_BT1120_D9/GMAC1_RXDV_CRS_M0/I2C5_SCL_M0/PDM_SDI0_M2/GPIO3_B3_D_AP6") (pintype "bidirectional+no_connect"))
    )
    (net (code "281") (name "unconnected-(U1D-VOP_BT1120_D10{slash}GMAC1_RXER_M0{slash}I2C5_SDA_M0{slash}PDM_SDI1_M2{slash}GPIO3_B4_D-Pad1U3)") (class "Default")
      (node (ref "U1") (pin "1U3") (pinfunction "VOP_BT1120_D10/GMAC1_RXER_M0/I2C5_SDA_M0/PDM_SDI1_M2/GPIO3_B4_D_1U3") (pintype "bidirectional+no_connect"))
    )
    (net (code "282") (name "unconnected-(U1D-VOP_BT1120_D11{slash}GMAC1_TXD0_M0{slash}I2C3_SCL_M1{slash}PWM10_M0{slash}GPIO3_B5_D-Pad1T4)") (class "Default")
      (node (ref "U1") (pin "1T4") (pinfunction "VOP_BT1120_D11/GMAC1_TXD0_M0/I2C3_SCL_M1/PWM10_M0/GPIO3_B5_D_1T4") (pintype "bidirectional+no_connect"))
    )
    (net (code "283") (name "unconnected-(U1D-VOP_BT1120_D12{slash}GMAC1_TXD1_M0{slash}I2C3_SDA_M1{slash}PWM11_IR_M0{slash}GPIO3_B6_D-Pad1V2)") (class "Default")
      (node (ref "U1") (pin "1V2") (pinfunction "VOP_BT1120_D12/GMAC1_TXD1_M0/I2C3_SDA_M1/PWM11_IR_M0/GPIO3_B6_D_1V2") (pintype "bidirectional+no_connect"))
    )
    (net (code "284") (name "unconnected-(U1D-VOP_BT1120_D13{slash}SPI1_MOSI_M1{slash}PCIE20_~{PERST}_M1{slash}I2S1_SDO2_M2{slash}GPIO3_C1_D-PadAP4)") (class "Default")
      (node (ref "U1") (pin "AP4") (pinfunction "VOP_BT1120_D13/SPI1_MOSI_M1/PCIE20_~{PERST}_M1/I2S1_SDO2_M2/GPIO3_C1_D_AP4") (pintype "bidirectional+no_connect"))
    )
    (net (code "285") (name "unconnected-(U1D-VOP_BT1120_D14{slash}SPI1_MISO_M1{slash}UART5_TX_M1{slash}I2S1_SDO3_M2{slash}GPIO3_C2_D-PadAP3)") (class "Default")
      (node (ref "U1") (pin "AP3") (pinfunction "VOP_BT1120_D14/SPI1_MISO_M1/UART5_TX_M1/I2S1_SDO3_M2/GPIO3_C2_D_AP3") (pintype "bidirectional+no_connect"))
    )
    (net (code "286") (name "unconnected-(U1D-VOP_BT1120_D15{slash}SPI1_CLK_M1{slash}UART5_RX_M1{slash}I2S1_SCLK_RX_M2{slash}GPIO3_C3_D-PadAR2)") (class "Default")
      (node (ref "U1") (pin "AR2") (pinfunction "VOP_BT1120_D15/SPI1_CLK_M1/UART5_RX_M1/I2S1_SCLK_RX_M2/GPIO3_C3_D_AR2") (pintype "bidirectional+no_connect"))
    )
    (net (code "287") (name "unconnected-(U1E-DDR_DM0_B{slash}DDR4_DMU_B{slash}LPDDR4_DM0_B{slash}DDR3_DM2{slash}LPDDR3_DM0-Pad1B8)") (class "Default")
      (node (ref "U1") (pin "1B8") (pinfunction "DDR_DM0_B/DDR4_DMU_B/LPDDR4_DM0_B/DDR3_DM2/LPDDR3_DM0_1B8") (pintype "bidirectional+no_connect"))
    )
    (net (code "288") (name "unconnected-(U1E-DDR_DM1_B{slash}DDR4_DML_B{slash}LPDDR4_DM1_B{slash}DDR3_DM3{slash}LPDDR3_DM2-Pad1A11)") (class "Default")
      (node (ref "U1") (pin "1A11") (pinfunction "DDR_DM1_B/DDR4_DML_B/LPDDR4_DM1_B/DDR3_DM3/LPDDR3_DM2_1A11") (pintype "bidirectional+no_connect"))
    )
    (net (code "289") (name "unconnected-(U1E-DDR_DQ0_B{slash}DDR4_DQU7_B{slash}LPDDR4_DQ0_B{slash}DDR3_DQ16{slash}LPDDR3_DQ1-PadB12)") (class "Default")
      (node (ref "U1") (pin "B12") (pinfunction "DDR_DQ0_B/DDR4_DQU7_B/LPDDR4_DQ0_B/DDR3_DQ16/LPDDR3_DQ1_B12") (pintype "bidirectional+no_connect"))
    )
    (net (code "290") (name "unconnected-(U1E-DDR_DQ1_B{slash}DDR4_DQU5_B{slash}LPDDR4_DQ1_B{slash}DDR3_DQ17{slash}LPDDR3_DQ5-PadB10)") (class "Default")
      (node (ref "U1") (pin "B10") (pinfunction "DDR_DQ1_B/DDR4_DQU5_B/LPDDR4_DQ1_B/DDR3_DQ17/LPDDR3_DQ5_B10") (pintype "bidirectional+no_connect"))
    )
    (net (code "291") (name "unconnected-(U1E-DDR_DQ2_B{slash}DDR4_DQU3_B{slash}LPDDR4_DQ2_B{slash}DDR3_DQ18{slash}LPDDR3_DQ6-Pad1A8)") (class "Default")
      (node (ref "U1") (pin "1A8") (pinfunction "DDR_DQ2_B/DDR4_DQU3_B/LPDDR4_DQ2_B/DDR3_DQ18/LPDDR3_DQ6_1A8") (pintype "bidirectional+no_connect"))
    )
    (net (code "292") (name "unconnected-(U1E-DDR_DQ3_B{slash}DDR4_DQU1_B{slash}LPDDR4_DQ3_B{slash}DDR3_DQ19{slash}LPDDR3_DQ4-Pad1A7)") (class "Default")
      (node (ref "U1") (pin "1A7") (pinfunction "DDR_DQ3_B/DDR4_DQU1_B/LPDDR4_DQ3_B/DDR3_DQ19/LPDDR3_DQ4_1A7") (pintype "bidirectional+no_connect"))
    )
    (net (code "293") (name "unconnected-(U1E-DDR_DQ4_B{slash}DDR4_DQU0_B{slash}LPDDR4_DQ4_B{slash}DDR3_DQ20{slash}LPDDR3_DQ2-PadB13)") (class "Default")
      (node (ref "U1") (pin "B13") (pinfunction "DDR_DQ4_B/DDR4_DQU0_B/LPDDR4_DQ4_B/DDR3_DQ20/LPDDR3_DQ2_B13") (pintype "bidirectional+no_connect"))
    )
    (net (code "294") (name "unconnected-(U1E-DDR_DQ5_B{slash}DDR4_DQU6_B{slash}LPDDR4_DQ5_B{slash}DDR3_DQ21{slash}LPDDR3_DQ3-Pad1A10)") (class "Default")
      (node (ref "U1") (pin "1A10") (pinfunction "DDR_DQ5_B/DDR4_DQU6_B/LPDDR4_DQ5_B/DDR3_DQ21/LPDDR3_DQ3_1A10") (pintype "bidirectional+no_connect"))
    )
    (net (code "295") (name "unconnected-(U1E-DDR_DQ6_B{slash}DDR4_DQU4_B{slash}LPDDR4_DQ6_B{slash}DDR3_DQ22{slash}LPDDR3_DQ7-Pad1B9)") (class "Default")
      (node (ref "U1") (pin "1B9") (pinfunction "DDR_DQ6_B/DDR4_DQU4_B/LPDDR4_DQ6_B/DDR3_DQ22/LPDDR3_DQ7_1B9") (pintype "bidirectional+no_connect"))
    )
    (net (code "296") (name "unconnected-(U1E-DDR_DQ7_B{slash}DDR4_DQU2_B{slash}LPDDR4_DQ7_B{slash}DDR3_DQ23{slash}LPDDR3_DQ0-Pad1A9)") (class "Default")
      (node (ref "U1") (pin "1A9") (pinfunction "DDR_DQ7_B/DDR4_DQU2_B/LPDDR4_DQ7_B/DDR3_DQ23/LPDDR3_DQ0_1A9") (pintype "bidirectional+no_connect"))
    )
    (net (code "297") (name "unconnected-(U1E-DDR_DQ8_B{slash}DDR4_DQL0_B{slash}LPDDR4_DQ8_B{slash}DDR3_DQ24{slash}LPDDR3_DQ18-PadB19)") (class "Default")
      (node (ref "U1") (pin "B19") (pinfunction "DDR_DQ8_B/DDR4_DQL0_B/LPDDR4_DQ8_B/DDR3_DQ24/LPDDR3_DQ18_B19") (pintype "bidirectional+no_connect"))
    )
    (net (code "298") (name "unconnected-(U1E-DDR_DQ9_B{slash}DDR4_DQL2_B{slash}LPDDR4_DQ9_B{slash}DDR3_DQ25{slash}LPDDR3_DQ19-PadA19)") (class "Default")
      (node (ref "U1") (pin "A19") (pinfunction "DDR_DQ9_B/DDR4_DQL2_B/LPDDR4_DQ9_B/DDR3_DQ25/LPDDR3_DQ19_A19") (pintype "bidirectional+no_connect"))
    )
    (net (code "299") (name "unconnected-(U1E-DDR_DQ10_B{slash}DDR4_DQL4_B{slash}LPDDR4_DQ10_B{slash}DDR3_DQ26{slash}LPDDR3_DQ22-PadA20)") (class "Default")
      (node (ref "U1") (pin "A20") (pinfunction "DDR_DQ10_B/DDR4_DQL4_B/LPDDR4_DQ10_B/DDR3_DQ26/LPDDR3_DQ22_A20") (pintype "bidirectional+no_connect"))
    )
    (net (code "300") (name "unconnected-(U1E-DDR_DQ11_B{slash}DDR4_DQL6_B{slash}LPDDR4_DQ11_B{slash}DDR3_DQ27{slash}LPDDR3_DQ23-PadB20)") (class "Default")
      (node (ref "U1") (pin "B20") (pinfunction "DDR_DQ11_B/DDR4_DQL6_B/LPDDR4_DQ11_B/DDR3_DQ27/LPDDR3_DQ23_B20") (pintype "bidirectional+no_connect"))
    )
    (net (code "301") (name "unconnected-(U1E-DDR_DQ12_B{slash}DDR4_DQL7_B{slash}LPDDR4_DQ12_B{slash}DDR3_DQ28{slash}LPDDR3_DQ16-PadA15)") (class "Default")
      (node (ref "U1") (pin "A15") (pinfunction "DDR_DQ12_B/DDR4_DQL7_B/LPDDR4_DQ12_B/DDR3_DQ28/LPDDR3_DQ16_A15") (pintype "bidirectional+no_connect"))
    )
    (net (code "302") (name "unconnected-(U1E-DDR_DQ13_B{slash}DDR4_DQL5_B{slash}LPDDR4_DQ13_B{slash}DDR3_DQ29{slash}LPDDR3_DQ17-PadB15)") (class "Default")
      (node (ref "U1") (pin "B15") (pinfunction "DDR_DQ13_B/DDR4_DQL5_B/LPDDR4_DQ13_B/DDR3_DQ29/LPDDR3_DQ17_B15") (pintype "bidirectional+no_connect"))
    )
    (net (code "303") (name "unconnected-(U1E-DDR_DQ14_B{slash}DDR4_DQL1_B{slash}LPDDR4_DQ14_B{slash}DDR3_DQ30{slash}LPDDR3_DQ20-Pad1C10)") (class "Default")
      (node (ref "U1") (pin "1C10") (pinfunction "DDR_DQ14_B/DDR4_DQL1_B/LPDDR4_DQ14_B/DDR3_DQ30/LPDDR3_DQ20_1C10") (pintype "bidirectional+no_connect"))
    )
    (net (code "304") (name "unconnected-(U1E-DDR_DQ15_B{slash}DDR4_DQL3_B{slash}LPDDR4_DQ15_B{slash}DDR3_DQ31{slash}LPDDR3_DQ21-PadB16)") (class "Default")
      (node (ref "U1") (pin "B16") (pinfunction "DDR_DQ15_B/DDR4_DQL3_B/LPDDR4_DQ15_B/DDR3_DQ31/LPDDR3_DQ21_B16") (pintype "bidirectional+no_connect"))
    )
    (net (code "305") (name "unconnected-(U1E-DDR_DQS1N_A{slash}DDR4_DQSU_N_A{slash}LPDDR4_DQS1N_A{slash}DDR3_DQS1N{slash}LPDDR3_DQS3N-PadN2)") (class "Default")
      (node (ref "U1") (pin "N2") (pinfunction "DDR_DQS1N_A/DDR4_DQSU_N_A/LPDDR4_DQS1N_A/DDR3_DQS1N/LPDDR3_DQS3N_N2") (pintype "bidirectional+no_connect"))
    )
    (net (code "306") (name "unconnected-(U1E-DDR_DQS1N_B{slash}DDR4_DQSL_N_B{slash}LPDDR4_DQS1N_B{slash}DDR3_DQS3N{slash}LPDDR3_DQS2N-PadB17)") (class "Default")
      (node (ref "U1") (pin "B17") (pinfunction "DDR_DQS1N_B/DDR4_DQSL_N_B/LPDDR4_DQS1N_B/DDR3_DQS3N/LPDDR3_DQS2N_B17") (pintype "bidirectional+no_connect"))
    )
    (net (code "307") (name "unconnected-(U1E-DDR_DQS1P_A{slash}DDR4_DQSU_P_A{slash}LPDDR4_DQS1P_A{slash}DDR3_DQS1P{slash}LPDDR3_DQS3P-PadN1)") (class "Default")
      (node (ref "U1") (pin "N1") (pinfunction "DDR_DQS1P_A/DDR4_DQSU_P_A/LPDDR4_DQS1P_A/DDR3_DQS1P/LPDDR3_DQS3P_N1") (pintype "bidirectional+no_connect"))
    )
    (net (code "308") (name "unconnected-(U1E-DDR_DQS1P_B{slash}DDR4_DQSL_P_B{slash}LPDDR4_DQS1P_B{slash}DDR3_DQS3P{slash}LPDDR3_DQS2P-PadA17)") (class "Default")
      (node (ref "U1") (pin "A17") (pinfunction "DDR_DQS1P_B/DDR4_DQSL_P_B/LPDDR4_DQS1P_B/DDR3_DQS3P/LPDDR3_DQS2P_A17") (pintype "bidirectional+no_connect"))
    )
    (net (code "309") (name "unconnected-(U1E-DDR_RZQ-Pad1F3)") (class "Default")
      (node (ref "U1") (pin "1F3") (pinfunction "DDR_RZQ_1F3") (pintype "bidirectional+no_connect"))
    )
    (net (code "310") (name "unconnected-(U1E-~{CS0}-Pad1B5)") (class "Default")
      (node (ref "U1") (pin "1B5") (pinfunction "~{CS0}_1B5") (pintype "bidirectional+no_connect"))
    )
    (net (code "311") (name "unconnected-(U1E-~{CS1}-Pad1A5)") (class "Default")
      (node (ref "U1") (pin "1A5") (pinfunction "~{CS1}_1A5") (pintype "bidirectional+no_connect"))
    )
    (net (code "312") (name "unconnected-(U1E-~{CS1}-PadA3)") (class "Default")
      (node (ref "U1") (pin "A3") (pinfunction "~{CS1}_A3") (pintype "bidirectional+no_connect"))
    )
  )
)
